# TopLevel.net
KiCad netlist of a schematic drawn in Altium Designer
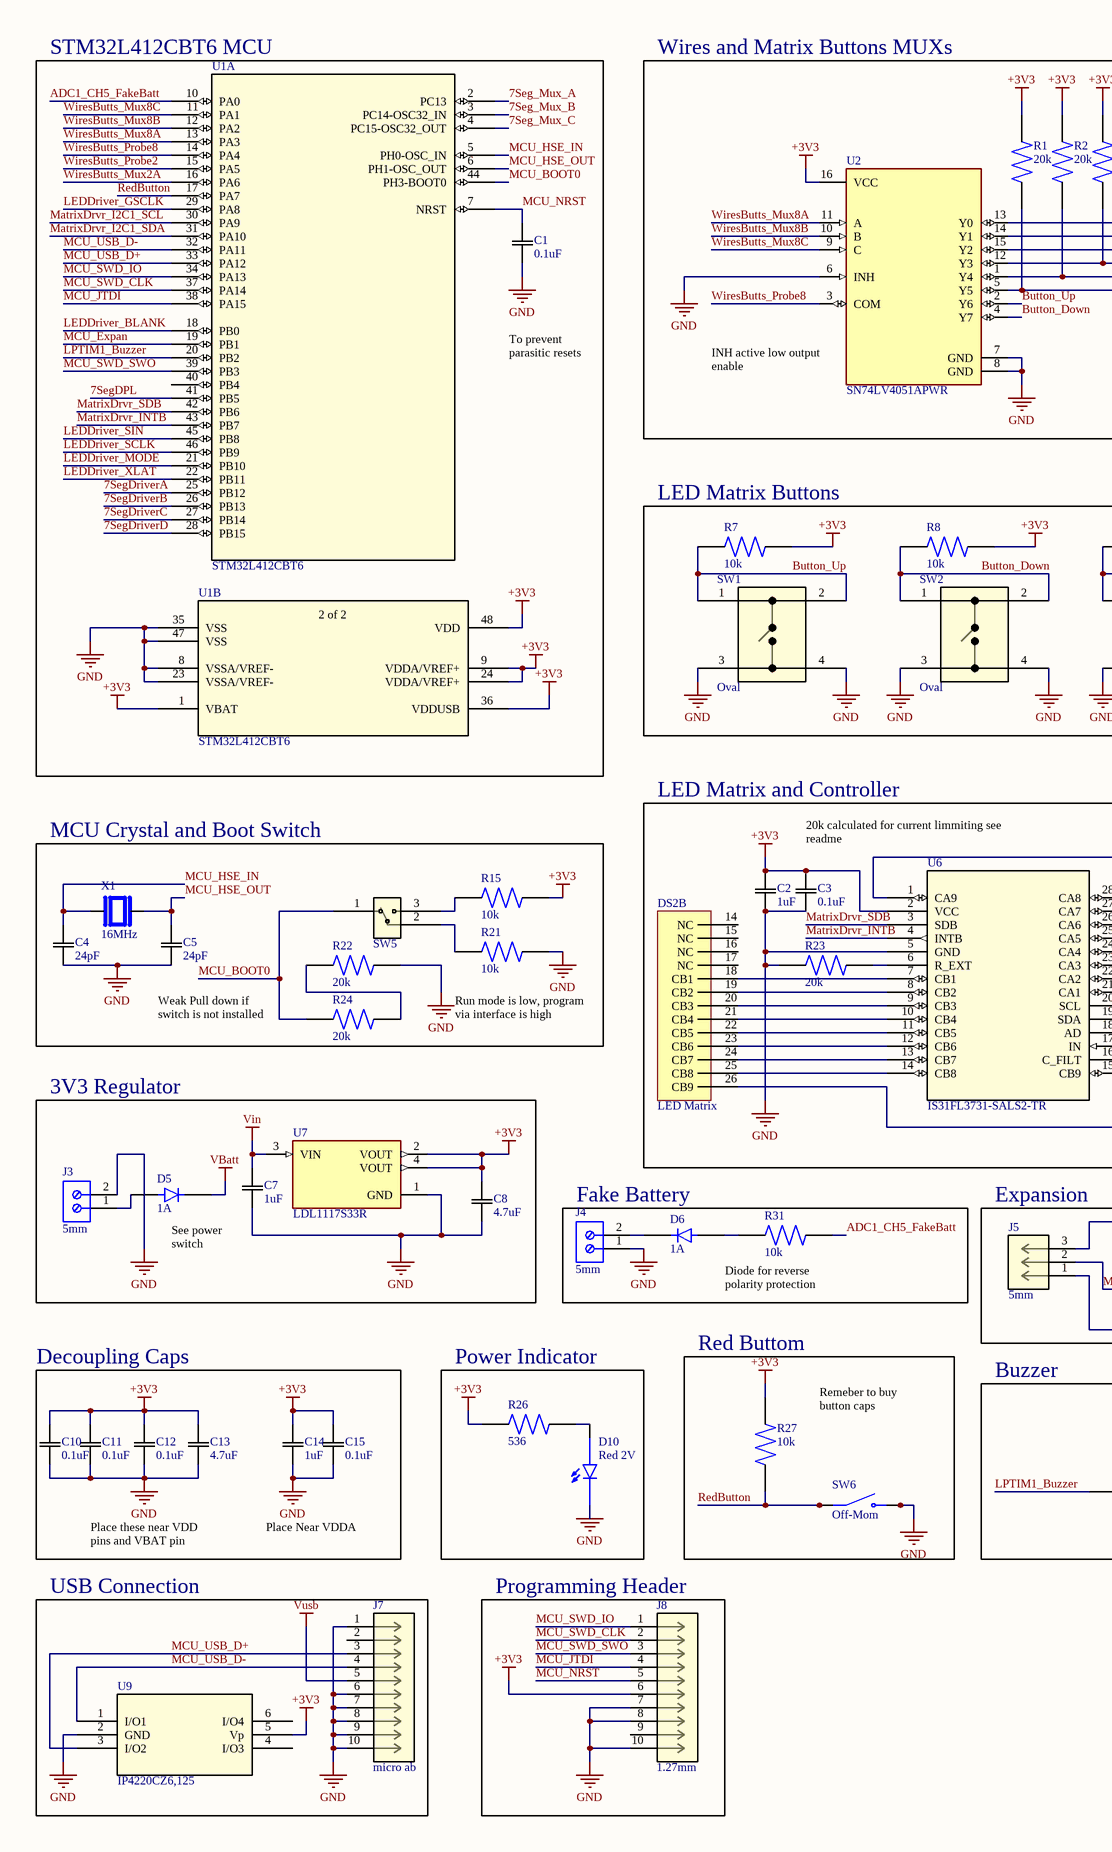
[diagram p0: TopLevel.SchDoc, left]
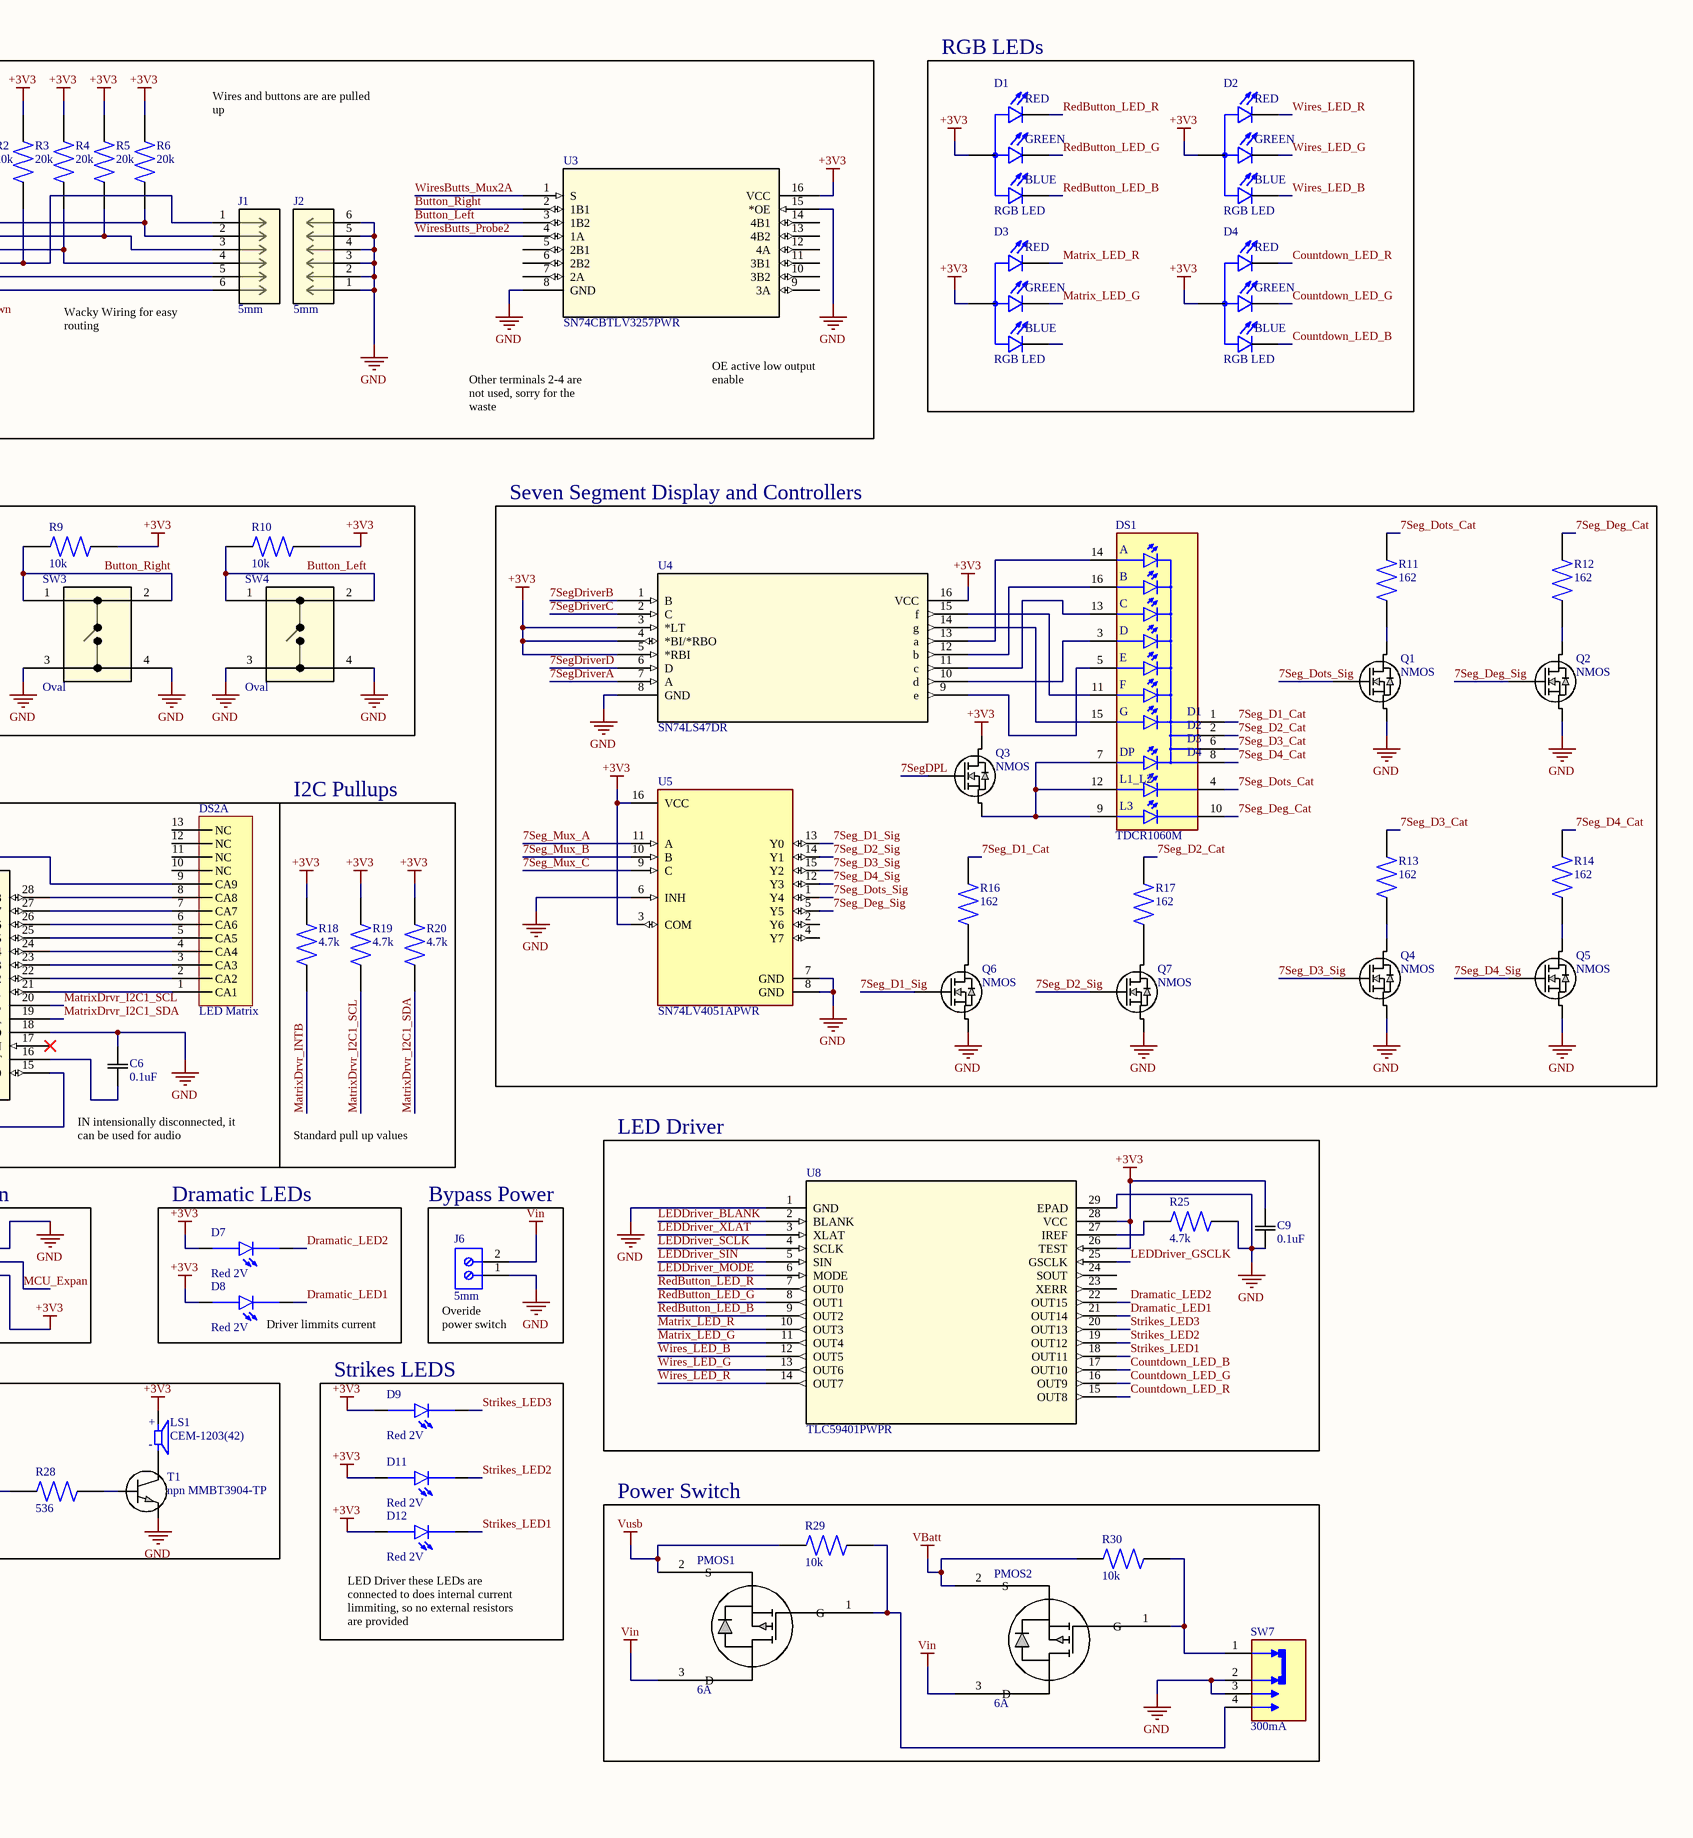
[diagram p1: TopLevel.SchDoc, right]

(export (version "E")
  (design (tool "Eeschema 10.0.6"))
  (components
    (comp (ref "C1")
      (value "0.1uF")
      (footprint "0805")
      (fields
        (field (name "MANUFACTURER") "Yageo")
        (field (name "MANUFACTURER PART NUMBER") "CC0805KRX7R9BB104")
      )
      (libsource (lib "Schlib1") (part "CAP CER 0.1uF 50V 0805"))
    )
    (comp (ref "C2")
      (value "1uF")
      (footprint "0805")
      (fields
        (field (name "MANUFACTURER") "Samsung")
        (field (name "MANUFACTURER PART NUMBER") "CL21B105KBFNNNE")
      )
      (libsource (lib "Schlib1") (part "CAP CER 1uF 50V 0805"))
    )
    (comp (ref "C3")
      (value "0.1uF")
      (footprint "0805")
      (fields
        (field (name "MANUFACTURER") "Yageo")
        (field (name "MANUFACTURER PART NUMBER") "CC0805KRX7R9BB104")
      )
      (libsource (lib "Schlib1") (part "CAP CER 0.1uF 50V 0805"))
    )
    (comp (ref "C4")
      (value "24pF")
      (footprint "0805")
      (description "CAP CER 24PF 50V NPO 0805")
      (fields
        (field (name "MANUFACTURER") "Yageo")
        (field (name "MANUFACTURER PART NUMBER") "CC0805JRNPO9BN240")
      )
      (libsource (lib "Schlib1") (part "CAP CER 24pF 5% 50V 0805"))
    )
    (comp (ref "C5")
      (value "24pF")
      (footprint "0805")
      (description "CAP CER 24PF 50V NPO 0805")
      (fields
        (field (name "MANUFACTURER") "Yageo")
        (field (name "MANUFACTURER PART NUMBER") "CC0805JRNPO9BN240")
      )
      (libsource (lib "Schlib1") (part "CAP CER 24pF 5% 50V 0805"))
    )
    (comp (ref "C6")
      (value "0.1uF")
      (footprint "0805")
      (fields
        (field (name "MANUFACTURER") "Yageo")
        (field (name "MANUFACTURER PART NUMBER") "CC0805KRX7R9BB104")
      )
      (libsource (lib "Schlib1") (part "CAP CER 0.1uF 50V 0805"))
    )
    (comp (ref "C7")
      (value "1uF")
      (footprint "0805")
      (fields
        (field (name "MANUFACTURER") "Samsung")
        (field (name "MANUFACTURER PART NUMBER") "CL21B105KBFNNNE")
      )
      (libsource (lib "Schlib1") (part "CAP CER 1uF 50V 0805"))
    )
    (comp (ref "C8")
      (value "4.7uF")
      (footprint "0805")
      (fields
        (field (name "MANUFACTURER") "Samsung")
        (field (name "MANUFACTURER PART NUMBER") "CL21A475KAQNNNE")
      )
      (libsource (lib "Schlib1") (part "CAP CER 4.7uF 50V 0805"))
    )
    (comp (ref "C9")
      (value "0.1uF")
      (footprint "0805")
      (fields
        (field (name "MANUFACTURER") "Yageo")
        (field (name "MANUFACTURER PART NUMBER") "CC0805KRX7R9BB104")
      )
      (libsource (lib "Schlib1") (part "CAP CER 0.1uF 50V 0805"))
    )
    (comp (ref "C10")
      (value "0.1uF")
      (footprint "0805")
      (fields
        (field (name "MANUFACTURER") "Yageo")
        (field (name "MANUFACTURER PART NUMBER") "CC0805KRX7R9BB104")
      )
      (libsource (lib "Schlib1") (part "CAP CER 0.1uF 50V 0805"))
    )
    (comp (ref "C11")
      (value "0.1uF")
      (footprint "0805")
      (fields
        (field (name "MANUFACTURER") "Yageo")
        (field (name "MANUFACTURER PART NUMBER") "CC0805KRX7R9BB104")
      )
      (libsource (lib "Schlib1") (part "CAP CER 0.1uF 50V 0805"))
    )
    (comp (ref "C12")
      (value "0.1uF")
      (footprint "0805")
      (fields
        (field (name "MANUFACTURER") "Yageo")
        (field (name "MANUFACTURER PART NUMBER") "CC0805KRX7R9BB104")
      )
      (libsource (lib "Schlib1") (part "CAP CER 0.1uF 50V 0805"))
    )
    (comp (ref "C13")
      (value "4.7uF")
      (footprint "0805")
      (fields
        (field (name "MANUFACTURER") "Samsung")
        (field (name "MANUFACTURER PART NUMBER") "CL21A475KAQNNNE")
      )
      (libsource (lib "Schlib1") (part "CAP CER 4.7uF 50V 0805"))
    )
    (comp (ref "C14")
      (value "1uF")
      (footprint "0805")
      (fields
        (field (name "MANUFACTURER") "Samsung")
        (field (name "MANUFACTURER PART NUMBER") "CL21B105KBFNNNE")
      )
      (libsource (lib "Schlib1") (part "CAP CER 1uF 50V 0805"))
    )
    (comp (ref "C15")
      (value "0.1uF")
      (footprint "0805")
      (fields
        (field (name "MANUFACTURER") "Yageo")
        (field (name "MANUFACTURER PART NUMBER") "CC0805KRX7R9BB104")
      )
      (libsource (lib "Schlib1") (part "CAP CER 0.1uF 50V 0805"))
    )
    (comp (ref "D1")
      (value "RGB LED")
      (footprint "RBG LED 4-SMD")
      (description "Visible LED")
      (fields
        (field (name "MANUFACTURER") "Cree")
        (field (name "MANUFACTURER PART NUMBER") "CLMVC-FKA-CL1D1L71BB7C3C3")
      )
      (libsource (lib "Schlib1") (part "DI LED RGB ComAnode"))
    )
    (comp (ref "D2")
      (value "RGB LED")
      (footprint "RBG LED 4-SMD")
      (description "Visible LED")
      (fields
        (field (name "MANUFACTURER") "Cree")
        (field (name "MANUFACTURER PART NUMBER") "CLMVC-FKA-CL1D1L71BB7C3C3")
      )
      (libsource (lib "Schlib1") (part "DI LED RGB ComAnode"))
    )
    (comp (ref "D3")
      (value "RGB LED")
      (footprint "RBG LED 4-SMD")
      (description "Visible LED")
      (fields
        (field (name "MANUFACTURER") "Cree")
        (field (name "MANUFACTURER PART NUMBER") "CLMVC-FKA-CL1D1L71BB7C3C3")
      )
      (libsource (lib "Schlib1") (part "DI LED RGB ComAnode"))
    )
    (comp (ref "D4")
      (value "RGB LED")
      (footprint "RBG LED 4-SMD")
      (description "Visible LED")
      (fields
        (field (name "MANUFACTURER") "Cree")
        (field (name "MANUFACTURER PART NUMBER") "CLMVC-FKA-CL1D1L71BB7C3C3")
      )
      (libsource (lib "Schlib1") (part "DI LED RGB ComAnode"))
    )
    (comp (ref "D5")
      (value "1A")
      (footprint "SOD-123F Diode Schottky")
      (description "Rectifier Diode, Schottky, 1 Phase, 1 Element, 1A, 25V V(RRM), Silicon")
      (fields (field (name "MANUFACTURER") "Rohm") (field (name "MANUFACTURER PART NUMBER") "RB161MM-20TR"))
      (libsource (lib "Schlib1") (part "Diode Schottky 25V 1A"))
    )
    (comp (ref "D6")
      (value "1A")
      (footprint "SOD-123F Diode Schottky")
      (description "Rectifier Diode, Schottky, 1 Phase, 1 Element, 1A, 25V V(RRM), Silicon")
      (fields (field (name "MANUFACTURER") "Rohm") (field (name "MANUFACTURER PART NUMBER") "RB161MM-20TR"))
      (libsource (lib "Schlib1") (part "Diode Schottky 25V 1A"))
    )
    (comp (ref "D7")
      (value "Red 2V")
      (footprint "0805")
      (description "Single Color LED, Red Orange, Water Clear, 1.4mm")
      (fields
        (field (name "MANUFACTURER") "Vishay Lite-On")
        (field (name "MANUFACTURER PART NUMBER") "LTST-C170KAKT")
      )
      (libsource (lib "Schlib1") (part "DIO LED RED 2V 0805"))
    )
    (comp (ref "D8")
      (value "Red 2V")
      (footprint "0805")
      (description "Single Color LED, Red Orange, Water Clear, 1.4mm")
      (fields
        (field (name "MANUFACTURER") "Vishay Lite-On")
        (field (name "MANUFACTURER PART NUMBER") "LTST-C170KAKT")
      )
      (libsource (lib "Schlib1") (part "DIO LED RED 2V 0805"))
    )
    (comp (ref "D9")
      (value "Red 2V")
      (footprint "0805")
      (description "Single Color LED, Red Orange, Water Clear, 1.4mm")
      (fields
        (field (name "MANUFACTURER") "Vishay Lite-On")
        (field (name "MANUFACTURER PART NUMBER") "LTST-C170KAKT")
      )
      (libsource (lib "Schlib1") (part "DIO LED RED 2V 0805"))
    )
    (comp (ref "D10")
      (value "Red 2V")
      (footprint "0805")
      (description "Single Color LED, Red Orange, Water Clear, 1.4mm")
      (fields
        (field (name "MANUFACTURER") "Vishay Lite-On")
        (field (name "MANUFACTURER PART NUMBER") "LTST-C170KAKT")
      )
      (libsource (lib "Schlib1") (part "DIO LED RED 2V 0805"))
    )
    (comp (ref "D11")
      (value "Red 2V")
      (footprint "0805")
      (description "Single Color LED, Red Orange, Water Clear, 1.4mm")
      (fields
        (field (name "MANUFACTURER") "Vishay Lite-On")
        (field (name "MANUFACTURER PART NUMBER") "LTST-C170KAKT")
      )
      (libsource (lib "Schlib1") (part "DIO LED RED 2V 0805"))
    )
    (comp (ref "D12")
      (value "Red 2V")
      (footprint "0805")
      (description "Single Color LED, Red Orange, Water Clear, 1.4mm")
      (fields
        (field (name "MANUFACTURER") "Vishay Lite-On")
        (field (name "MANUFACTURER PART NUMBER") "LTST-C170KAKT")
      )
      (libsource (lib "Schlib1") (part "DIO LED RED 2V 0805"))
    )
    (comp (ref "DS1")
      (value "TDCR1060M")
      (footprint "16-DIP 4Char-7Seg")
      (description "Clock LED Display, 4-Character, Red, 10mm")
      (fields (field (name "MANUFACTURER") "Vishay"))
      (libsource (lib "Schlib1") (part "DISP 7-seg 4Char Clock"))
    )
    (comp (ref "DS2")
      (value "LED Matrix")
      (footprint "LED Matrix 9x16 Charlie")
      (libsource (lib "") (part "LEDARR 2973 9X16_1"))
    )
    (comp (ref "J1")
      (value "5mm")
      (footprint "CON 6pos Screw 5.00mm")
      (description "Barrier Strip Terminal Block, 17.5A, 2.5mm2, 1 Row(s), 1 Deck(s)")
      (fields
        (field (name "MANUFACTURER") "Phoenix Contact")
        (field (name "MANUFACTURER PART NUMBER") "1988846")
        (field (name "SAFETY APPROVAL") "UL")
      )
      (libsource (lib "Schlib1") (part "CONN SCREW 6pos 45Deg 5mm"))
    )
    (comp (ref "J2")
      (value "5mm")
      (footprint "CON 6pos Screw 5.00mm")
      (description "Barrier Strip Terminal Block, 17.5A, 2.5mm2, 1 Row(s), 1 Deck(s)")
      (fields
        (field (name "MANUFACTURER") "Phoenix Contact")
        (field (name "MANUFACTURER PART NUMBER") "1988846")
        (field (name "SAFETY APPROVAL") "UL")
      )
      (libsource (lib "") (part "CONN SCREW 6pos 45Deg 5mm_1"))
    )
    (comp (ref "J3")
      (value "5mm")
      (footprint "Con 2Pos Screw 5.00mm")
      (description "Barrier Strip Terminal Block")
      (fields
        (field (name "MANUFACTURER") "Wurth Electronics")
        (field (name "MANUFACTURER PART NUMBER") "691137710002")
      )
      (libsource (lib "Schlib1") (part "CON Screw 2Pos 5.00mm"))
    )
    (comp (ref "J4")
      (value "5mm")
      (footprint "Con 2Pos Screw 5.00mm")
      (description "Barrier Strip Terminal Block")
      (fields
        (field (name "MANUFACTURER") "Wurth Electronics")
        (field (name "MANUFACTURER PART NUMBER") "691137710002")
      )
      (libsource (lib "Schlib1") (part "CON Screw 2Pos 5.00mm"))
    )
    (comp (ref "J5")
      (value "5mm")
      (footprint "CONN 3pos 5.00mm")
      (description "Barrier Strip Terminal Block, 17.5A, 1.5mm2, 1 Row(s), 1 Deck(s)")
      (fields
        (field (name "MANUFACTURER") "Phoenix Contact")
        (field (name "MANUFACTURER PART NUMBER") "1935174")
        (field (name "SAFETY APPROVAL") "UL")
      )
      (libsource (lib "Schlib1") (part "CONN SCREW 3pos 5.0mm"))
    )
    (comp (ref "J6")
      (value "5mm")
      (footprint "Con 2Pos Screw 5.00mm")
      (description "Barrier Strip Terminal Block")
      (fields
        (field (name "MANUFACTURER") "Wurth Electronics")
        (field (name "MANUFACTURER PART NUMBER") "691137710002")
      )
      (libsource (lib "Schlib1") (part "CON Screw 2Pos 5.00mm"))
    )
    (comp (ref "J7")
      (value "micro ab")
      (footprint "USB micro ab 0475900001")
      (description "USB Connector, 5 Contact(s), Female, Right Angle, Surface Mount Terminal, Locking, Receptacle")
      (fields (field (name "MANUFACTURER") "Molex") (field (name "MANUFACTURER PART NUMBER") "47590-0001"))
      (libsource (lib "Schlib1") (part "CON USB micro ab"))
    )
    (comp (ref "J8")
      (value "1.27mm")
      (footprint "Con 10pin 2Row 1.27mm")
      (fields
        (field (name "MANUFACTURER") "Toshiba")
        (field (name "MANUFACTURER PART NUMBER") "SSM3J372R,LF")
      )
      (libsource (lib "Schlib1") (part "Con 10pos 2row Header 1.27mm Surface"))
    )
    (comp (ref "LS1")
      (value "CEM-1203(42)")
      (footprint "Buzzer CEM-1203(42)")
      (description "Audio Signaling/Alarm Devices")
      (fields (field (name "MANUFACTURER") "Same Sky"))
      (libsource (lib "Schlib1") (part "LS Buzzer CEM-1203(42)"))
    )
    (comp (ref "PMOS1")
      (value "6A")
      (footprint "SOT-23F MOS PMOS 30V 6A")
      (fields
        (field (name "MANUFACTURER") "Toshiba")
        (field (name "MANUFACTURER PART NUMBER") "SSM3J372R,LF")
      )
      (libsource (lib "Schlib1") (part "MOS PMOS 30V 6A"))
    )
    (comp (ref "PMOS2")
      (value "6A")
      (footprint "SOT-23F MOS PMOS 30V 6A")
      (fields
        (field (name "MANUFACTURER") "Toshiba")
        (field (name "MANUFACTURER PART NUMBER") "SSM3J372R,LF")
      )
      (libsource (lib "Schlib1") (part "MOS PMOS 30V 6A"))
    )
    (comp (ref "Q1")
      (value "NMOS")
      (footprint "SOT-323 MOS")
      (fields
        (field (name "MANUFACTURER") "Diodes Zetex")
        (field (name "MANUFACTURER PART NUMBER") "DMG1012UW-7")
      )
      (libsource (lib "Schlib1") (part "MOS NMOS 20V 1A SOT323"))
    )
    (comp (ref "Q2")
      (value "NMOS")
      (footprint "SOT-323 MOS")
      (fields
        (field (name "MANUFACTURER") "Diodes Zetex")
        (field (name "MANUFACTURER PART NUMBER") "DMG1012UW-7")
      )
      (libsource (lib "Schlib1") (part "MOS NMOS 20V 1A SOT323"))
    )
    (comp (ref "Q3")
      (value "NMOS")
      (footprint "SOT-323 MOS")
      (fields
        (field (name "MANUFACTURER") "Diodes Zetex")
        (field (name "MANUFACTURER PART NUMBER") "DMG1012UW-7")
      )
      (libsource (lib "Schlib1") (part "MOS NMOS 20V 1A SOT323"))
    )
    (comp (ref "Q4")
      (value "NMOS")
      (footprint "SOT-323 MOS")
      (fields
        (field (name "MANUFACTURER") "Diodes Zetex")
        (field (name "MANUFACTURER PART NUMBER") "DMG1012UW-7")
      )
      (libsource (lib "Schlib1") (part "MOS NMOS 20V 1A SOT323"))
    )
    (comp (ref "Q5")
      (value "NMOS")
      (footprint "SOT-323 MOS")
      (fields
        (field (name "MANUFACTURER") "Diodes Zetex")
        (field (name "MANUFACTURER PART NUMBER") "DMG1012UW-7")
      )
      (libsource (lib "Schlib1") (part "MOS NMOS 20V 1A SOT323"))
    )
    (comp (ref "Q6")
      (value "NMOS")
      (footprint "SOT-323 MOS")
      (fields
        (field (name "MANUFACTURER") "Diodes Zetex")
        (field (name "MANUFACTURER PART NUMBER") "DMG1012UW-7")
      )
      (libsource (lib "Schlib1") (part "MOS NMOS 20V 1A SOT323"))
    )
    (comp (ref "Q7")
      (value "NMOS")
      (footprint "SOT-323 MOS")
      (fields
        (field (name "MANUFACTURER") "Diodes Zetex")
        (field (name "MANUFACTURER PART NUMBER") "DMG1012UW-7")
      )
      (libsource (lib "Schlib1") (part "MOS NMOS 20V 1A SOT323"))
    )
    (comp (ref "R1")
      (value "20k")
      (footprint "0805")
      (description "Fixed Resistor, Thin Film, 0.125W, 20000ohm, 150V, 0.1% +/-Tol, 25ppm/Cel, Surface Mount, 0805")
      (fields
        (field (name "MANUFACTURER") "Susumu")
        (field (name "MANUFACTURER PART NUMBER") "RG2012P-203-B-T5")
      )
      (libsource (lib "Schlib1") (part "RES 20K 0.1% 0.125W 0805"))
    )
    (comp (ref "R2")
      (value "20k")
      (footprint "0805")
      (description "Fixed Resistor, Thin Film, 0.125W, 20000ohm, 150V, 0.1% +/-Tol, 25ppm/Cel, Surface Mount, 0805")
      (fields
        (field (name "MANUFACTURER") "Susumu")
        (field (name "MANUFACTURER PART NUMBER") "RG2012P-203-B-T5")
      )
      (libsource (lib "Schlib1") (part "RES 20K 0.1% 0.125W 0805"))
    )
    (comp (ref "R3")
      (value "20k")
      (footprint "0805")
      (description "Fixed Resistor, Thin Film, 0.125W, 20000ohm, 150V, 0.1% +/-Tol, 25ppm/Cel, Surface Mount, 0805")
      (fields
        (field (name "MANUFACTURER") "Susumu")
        (field (name "MANUFACTURER PART NUMBER") "RG2012P-203-B-T5")
      )
      (libsource (lib "Schlib1") (part "RES 20K 0.1% 0.125W 0805"))
    )
    (comp (ref "R4")
      (value "20k")
      (footprint "0805")
      (description "Fixed Resistor, Thin Film, 0.125W, 20000ohm, 150V, 0.1% +/-Tol, 25ppm/Cel, Surface Mount, 0805")
      (fields
        (field (name "MANUFACTURER") "Susumu")
        (field (name "MANUFACTURER PART NUMBER") "RG2012P-203-B-T5")
      )
      (libsource (lib "Schlib1") (part "RES 20K 0.1% 0.125W 0805"))
    )
    (comp (ref "R5")
      (value "20k")
      (footprint "0805")
      (description "Fixed Resistor, Thin Film, 0.125W, 20000ohm, 150V, 0.1% +/-Tol, 25ppm/Cel, Surface Mount, 0805")
      (fields
        (field (name "MANUFACTURER") "Susumu")
        (field (name "MANUFACTURER PART NUMBER") "RG2012P-203-B-T5")
      )
      (libsource (lib "Schlib1") (part "RES 20K 0.1% 0.125W 0805"))
    )
    (comp (ref "R6")
      (value "20k")
      (footprint "0805")
      (description "Fixed Resistor, Thin Film, 0.125W, 20000ohm, 150V, 0.1% +/-Tol, 25ppm/Cel, Surface Mount, 0805")
      (fields
        (field (name "MANUFACTURER") "Susumu")
        (field (name "MANUFACTURER PART NUMBER") "RG2012P-203-B-T5")
      )
      (libsource (lib "Schlib1") (part "RES 20K 0.1% 0.125W 0805"))
    )
    (comp (ref "R7")
      (value "10k")
      (footprint "0805")
      (fields
        (field (name "MANUFACTURER") "Panasonic")
        (field (name "MANUFACTURER PART NUMBER") "ERJ-6GEYJ103V")
        (field (name "TOLERANCE") "5%")
      )
      (libsource (lib "Schlib1") (part "RES 10k 5% 0.125W 0805"))
    )
    (comp (ref "R8")
      (value "10k")
      (footprint "0805")
      (fields
        (field (name "MANUFACTURER") "Panasonic")
        (field (name "MANUFACTURER PART NUMBER") "ERJ-6GEYJ103V")
        (field (name "TOLERANCE") "5%")
      )
      (libsource (lib "Schlib1") (part "RES 10k 5% 0.125W 0805"))
    )
    (comp (ref "R9")
      (value "10k")
      (footprint "0805")
      (fields
        (field (name "MANUFACTURER") "Panasonic")
        (field (name "MANUFACTURER PART NUMBER") "ERJ-6GEYJ103V")
        (field (name "TOLERANCE") "5%")
      )
      (libsource (lib "Schlib1") (part "RES 10k 5% 0.125W 0805"))
    )
    (comp (ref "R10")
      (value "10k")
      (footprint "0805")
      (fields
        (field (name "MANUFACTURER") "Panasonic")
        (field (name "MANUFACTURER PART NUMBER") "ERJ-6GEYJ103V")
        (field (name "TOLERANCE") "5%")
      )
      (libsource (lib "Schlib1") (part "RES 10k 5% 0.125W 0805"))
    )
    (comp (ref "R11")
      (value "162")
      (footprint "0805")
      (fields
        (field (name "MANUFACTURER") "Yageo")
        (field (name "MANUFACTURER PART NUMBER") "RC0805FR-07162RL")
        (field (name "TOLERANCE") "1%")
      )
      (libsource (lib "Schlib1") (part "RES 162 1% 0.125W 0805"))
    )
    (comp (ref "R12")
      (value "162")
      (footprint "0805")
      (fields
        (field (name "MANUFACTURER") "Yageo")
        (field (name "MANUFACTURER PART NUMBER") "RC0805FR-07162RL")
        (field (name "TOLERANCE") "1%")
      )
      (libsource (lib "Schlib1") (part "RES 162 1% 0.125W 0805"))
    )
    (comp (ref "R13")
      (value "162")
      (footprint "0805")
      (fields
        (field (name "MANUFACTURER") "Yageo")
        (field (name "MANUFACTURER PART NUMBER") "RC0805FR-07162RL")
        (field (name "TOLERANCE") "1%")
      )
      (libsource (lib "Schlib1") (part "RES 162 1% 0.125W 0805"))
    )
    (comp (ref "R14")
      (value "162")
      (footprint "0805")
      (fields
        (field (name "MANUFACTURER") "Yageo")
        (field (name "MANUFACTURER PART NUMBER") "RC0805FR-07162RL")
        (field (name "TOLERANCE") "1%")
      )
      (libsource (lib "Schlib1") (part "RES 162 1% 0.125W 0805"))
    )
    (comp (ref "R15")
      (value "10k")
      (footprint "0805")
      (fields
        (field (name "MANUFACTURER") "Panasonic")
        (field (name "MANUFACTURER PART NUMBER") "ERJ-6GEYJ103V")
        (field (name "TOLERANCE") "5%")
      )
      (libsource (lib "Schlib1") (part "RES 10k 5% 0.125W 0805"))
    )
    (comp (ref "R16")
      (value "162")
      (footprint "0805")
      (fields
        (field (name "MANUFACTURER") "Yageo")
        (field (name "MANUFACTURER PART NUMBER") "RC0805FR-07162RL")
        (field (name "TOLERANCE") "1%")
      )
      (libsource (lib "Schlib1") (part "RES 162 1% 0.125W 0805"))
    )
    (comp (ref "R17")
      (value "162")
      (footprint "0805")
      (fields
        (field (name "MANUFACTURER") "Yageo")
        (field (name "MANUFACTURER PART NUMBER") "RC0805FR-07162RL")
        (field (name "TOLERANCE") "1%")
      )
      (libsource (lib "Schlib1") (part "RES 162 1% 0.125W 0805"))
    )
    (comp (ref "R18")
      (value "4.7k")
      (footprint "0805")
      (fields
        (field (name "MANUFACTURER") "Vishay")
        (field (name "MANUFACTURER PART NUMBER") "CRCW08054K70FKEA")
        (field (name "TOLERANCE") "1%")
      )
      (libsource (lib "Schlib1") (part "RES 4.7k 1% 0.125W 0805"))
    )
    (comp (ref "R19")
      (value "4.7k")
      (footprint "0805")
      (fields
        (field (name "MANUFACTURER") "Vishay")
        (field (name "MANUFACTURER PART NUMBER") "CRCW08054K70FKEA")
        (field (name "TOLERANCE") "1%")
      )
      (libsource (lib "Schlib1") (part "RES 4.7k 1% 0.125W 0805"))
    )
    (comp (ref "R20")
      (value "4.7k")
      (footprint "0805")
      (fields
        (field (name "MANUFACTURER") "Vishay")
        (field (name "MANUFACTURER PART NUMBER") "CRCW08054K70FKEA")
        (field (name "TOLERANCE") "1%")
      )
      (libsource (lib "Schlib1") (part "RES 4.7k 1% 0.125W 0805"))
    )
    (comp (ref "R21")
      (value "10k")
      (footprint "0805")
      (fields
        (field (name "MANUFACTURER") "Panasonic")
        (field (name "MANUFACTURER PART NUMBER") "ERJ-6GEYJ103V")
        (field (name "TOLERANCE") "5%")
      )
      (libsource (lib "Schlib1") (part "RES 10k 5% 0.125W 0805"))
    )
    (comp (ref "R22")
      (value "20k")
      (footprint "0805")
      (description "Fixed Resistor, Thin Film, 0.125W, 20000ohm, 150V, 0.1% +/-Tol, 25ppm/Cel, Surface Mount, 0805")
      (fields
        (field (name "MANUFACTURER") "Susumu")
        (field (name "MANUFACTURER PART NUMBER") "RG2012P-203-B-T5")
      )
      (libsource (lib "Schlib1") (part "RES 20K 0.1% 0.125W 0805"))
    )
    (comp (ref "R23")
      (value "20k")
      (footprint "0805")
      (description "Fixed Resistor, Thin Film, 0.125W, 20000ohm, 150V, 0.1% +/-Tol, 25ppm/Cel, Surface Mount, 0805")
      (fields
        (field (name "MANUFACTURER") "Susumu")
        (field (name "MANUFACTURER PART NUMBER") "RG2012P-203-B-T5")
      )
      (libsource (lib "Schlib1") (part "RES 20K 0.1% 0.125W 0805"))
    )
    (comp (ref "R24")
      (value "20k")
      (footprint "0805")
      (description "Fixed Resistor, Thin Film, 0.125W, 20000ohm, 150V, 0.1% +/-Tol, 25ppm/Cel, Surface Mount, 0805")
      (fields
        (field (name "MANUFACTURER") "Susumu")
        (field (name "MANUFACTURER PART NUMBER") "RG2012P-203-B-T5")
      )
      (libsource (lib "Schlib1") (part "RES 20K 0.1% 0.125W 0805"))
    )
    (comp (ref "R25")
      (value "4.7k")
      (footprint "0805")
      (fields
        (field (name "MANUFACTURER") "Vishay")
        (field (name "MANUFACTURER PART NUMBER") "CRCW08054K70FKEA")
        (field (name "TOLERANCE") "1%")
      )
      (libsource (lib "Schlib1") (part "RES 4.7k 1% 0.125W 0805"))
    )
    (comp (ref "R26")
      (value "536")
      (footprint "0805")
      (fields
        (field (name "MANUFACTURER") "Yageo")
        (field (name "MANUFACTURER PART NUMBER") "RC0805FR-07536RL")
        (field (name "TOLERANCE") "1%")
      )
      (libsource (lib "Schlib1") (part "RES 536 1% 0.125W 0805"))
    )
    (comp (ref "R27")
      (value "10k")
      (footprint "0805")
      (fields
        (field (name "MANUFACTURER") "Panasonic")
        (field (name "MANUFACTURER PART NUMBER") "ERJ-6GEYJ103V")
        (field (name "TOLERANCE") "5%")
      )
      (libsource (lib "Schlib1") (part "RES 10k 5% 0.125W 0805"))
    )
    (comp (ref "R28")
      (value "536")
      (footprint "0805")
      (fields
        (field (name "MANUFACTURER") "Yageo")
        (field (name "MANUFACTURER PART NUMBER") "RC0805FR-07536RL")
        (field (name "TOLERANCE") "1%")
      )
      (libsource (lib "Schlib1") (part "RES 536 1% 0.125W 0805"))
    )
    (comp (ref "R29")
      (value "10k")
      (footprint "0805")
      (fields
        (field (name "MANUFACTURER") "Panasonic")
        (field (name "MANUFACTURER PART NUMBER") "ERJ-6GEYJ103V")
        (field (name "TOLERANCE") "5%")
      )
      (libsource (lib "Schlib1") (part "RES 10k 5% 0.125W 0805"))
    )
    (comp (ref "R30")
      (value "10k")
      (footprint "0805")
      (fields
        (field (name "MANUFACTURER") "Panasonic")
        (field (name "MANUFACTURER PART NUMBER") "ERJ-6GEYJ103V")
        (field (name "TOLERANCE") "5%")
      )
      (libsource (lib "Schlib1") (part "RES 10k 5% 0.125W 0805"))
    )
    (comp (ref "R31")
      (value "10k")
      (footprint "0805")
      (fields
        (field (name "MANUFACTURER") "Panasonic")
        (field (name "MANUFACTURER PART NUMBER") "ERJ-6GEYJ103V")
        (field (name "TOLERANCE") "5%")
      )
      (libsource (lib "Schlib1") (part "RES 10k 5% 0.125W 0805"))
    )
    (comp (ref "SW1")
      (value "Oval")
      (footprint "Oval Button")
      (fields
        (field (name "MANUFACTURER") "E-Switch")
        (field (name "MANUFACTURER PART NUMBER") "TL3365AF180QG")
      )
      (libsource (lib "Schlib1") (part "SW Off-Mom OvalPush"))
    )
    (comp (ref "SW2")
      (value "Oval")
      (footprint "Oval Button")
      (fields
        (field (name "MANUFACTURER") "E-Switch")
        (field (name "MANUFACTURER PART NUMBER") "TL3365AF180QG")
      )
      (libsource (lib "Schlib1") (part "SW Off-Mom OvalPush"))
    )
    (comp (ref "SW3")
      (value "Oval")
      (footprint "Oval Button")
      (fields
        (field (name "MANUFACTURER") "E-Switch")
        (field (name "MANUFACTURER PART NUMBER") "TL3365AF180QG")
      )
      (libsource (lib "Schlib1") (part "SW Off-Mom OvalPush"))
    )
    (comp (ref "SW4")
      (value "Oval")
      (footprint "Oval Button")
      (fields
        (field (name "MANUFACTURER") "E-Switch")
        (field (name "MANUFACTURER PART NUMBER") "TL3365AF180QG")
      )
      (libsource (lib "Schlib1") (part "SW Off-Mom OvalPush"))
    )
    (comp (ref "SW5")
      (value "OS102011MA1QN1")
      (footprint "OS102011MA1QN1")
      (fields
        (field (name "MANUFACTURER") "ITT C&K")
        (field (name "MANUFACTURER PART NUMBER") "OS102011MA1QN1C")
      )
      (libsource (lib "Schlib1") (part "SW 2pos Through RightAngle"))
    )
    (comp (ref "SW6")
      (value "Off-Mom")
      (footprint "Switch off-Mom")
      (description "Pushbutton Switch, SPST, Momentary-tactile, 0.05A, Solder Terminal, Through Hole-straight")
      (fields
        (field (name "MANUFACTURER") "TE Connectivity Alcoswitch")
        (field (name "MANUFACTURER PART NUMBER") "FSM103")
      )
      (libsource (lib "Schlib1") (part "SW Off-Mom Through"))
    )
    (comp (ref "SW7")
      (value "300mA")
      (footprint "Switch On-On-On 300mA SLW-1277545-2A-RA-S-D")
      (description "12.7 x 7.5 x 4.5 mm, 2 mm Raised Slide Actuator, Right Angle, Through Hole, Slide Switch")
      (fields
        (field (name "MANUFACTURER") "Same Sky")
        (field (name "MANUFACTURER PART NUMBER") "SLW-1277545-2A-RA-S-D")
      )
      (libsource (lib "Schlib1") (part "SW On-On-On 300mA"))
    )
    (comp (ref "T1")
      (value "npn MMBT3904-TP")
      (footprint "SOT-23 Transistor")
      (description "Small Signal Bipolar Transistor, 0.2A I(C), 40V V(BR)CEO, 1-Element, NPN, Silicon")
      (fields (field (name "MANUFACTURER") "MCC") (field (name "MANUFACTURER PART NUMBER") "MMBT3904-TP"))
      (libsource (lib "Schlib1") (part "T npn 40V 0.2A"))
    )
    (comp (ref "U1")
      (value "STM32L412CBT6")
      (footprint "48-LQFP")
      (description "RISC Microcontroller")
      (fields (field (name "MANUFACTURER") "STMicroelectronics"))
      (libsource (lib "Schlib1") (part "IC STM32L412CBT6"))
    )
    (comp (ref "U2")
      (value "SN74LV4051APWR")
      (footprint "16-TSSOP MUX 8to1")
      (description "Single-Ended Multiplexer, 1 Func, 8 Channel, CMOS, PDSO16")
      (fields (field (name "MANUFACTURER") "Texas Instruments"))
      (libsource (lib "Schlib1") (part "IC MUX 8{colon}1 SN74LV4051APWR"))
    )
    (comp (ref "U3")
      (value "SN74CBTLV3257PWR")
      (footprint "16-TSSOP 1:2 switch SN74CBTLV3257PWR")
      (fields (field (name "MANUFACTURER") "Texas Instruments"))
      (libsource (lib "Schlib1") (part "IC 1{colon}2 Switch SN74CBTLV3257PWR"))
    )
    (comp (ref "U4")
      (value "SN74LS47DR")
      (footprint "16-SOIC 7-seg Driver")
      (description "Seven Segment Decoder/Driver, LS Series, Inverted Output, TTL, PDSO16")
      (fields (field (name "MANUFACTURER") "Texas Instruments"))
      (libsource (lib "Schlib1") (part "IC DRVR 7 SEG SN74LS47DR"))
    )
    (comp (ref "U5")
      (value "SN74LV4051APWR")
      (footprint "16-TSSOP MUX 8to1")
      (description "Single-Ended Multiplexer, 1 Func, 8 Channel, CMOS, PDSO16")
      (fields (field (name "MANUFACTURER") "Texas Instruments"))
      (libsource (lib "Schlib1") (part "IC MUX 8{colon}1 SN74LV4051APWR"))
    )
    (comp (ref "U6")
      (value "IS31FL3731-SALS2-TR")
      (footprint "28-SSOP LED Matrix Driver")
      (description "LED Driver, 144-Segment, PDSO28")
      (fields (field (name "MANUFACTURER") "ISSI"))
      (libsource (lib "Schlib1") (part "IC MatrixDriv IS31FL3731-SALS2-TR"))
    )
    (comp (ref "U7")
      (value "LDL1117S33R")
      (footprint "SOT-223 Lin Reg 3V3")
      (description "Fixed Positive LDO Regulator, 3.3V, 0.6V Dropout, PDSO4")
      (fields (field (name "MANUFACTURER") "STMicroelectronics"))
      (libsource (lib "Schlib1") (part "IC LIN REG 3V3 LDL1117S33R"))
    )
    (comp (ref "U8")
      (value "TLC59401PWPR")
      (footprint "28-HTSSOP 16LED Driver")
      (description "LED Driver, 16-Segment, PDSO28")
      (fields (field (name "MANUFACTURER") "Texas Instruments"))
      (libsource (lib "Schlib1") (part "IC 16LED Driver TLC59401PWPR"))
    )
    (comp (ref "U9")
      (value "IP4220CZ6,125")
      (footprint "SOT-457 USB ESD")
      (description "Trans Voltage Suppressor Diode, Unidirectional, 1 Element, Silicon")
      (fields (field (name "MANUFACTURER") "Nexperia"))
      (libsource (lib "Schlib1") (part "IC USB Dual ESD Protec IP4220CZ6,125"))
    )
    (comp (ref "X1")
      (value "16MHz")
      (footprint "OSC 16MHz")
      (description "Crystal 16MHz ±20ppm (Tol) ±50ppm (Stability) 18pF FUND 40Ohm 2-Pin HC-49/US SMD T/R")
      (fields
        (field (name "MANUFACTURER") "Abracon")
        (field (name "MANUFACTURER PART NUMBER") "ABLS-16.000MHZ-B2-T")
      )
      (libsource (lib "Schlib1") (part "OSC 16MHz 18pF"))
    )
  )
  (nets
    (net (code "1") (name "+3V3") (class "Default")
      (node (ref "C10") (pin "2") (pinfunction "2_2") (pintype "passive"))
      (node (ref "C11") (pin "2") (pinfunction "2_2") (pintype "passive"))
      (node (ref "C12") (pin "2") (pinfunction "2_2") (pintype "passive"))
      (node (ref "C13") (pin "2") (pinfunction "2_2") (pintype "passive"))
      (node (ref "C14") (pin "1") (pinfunction "1_1") (pintype "passive"))
      (node (ref "C15") (pin "2") (pinfunction "2_2") (pintype "passive"))
      (node (ref "C2") (pin "2") (pinfunction "2_2") (pintype "passive"))
      (node (ref "C3") (pin "2") (pinfunction "2_2") (pintype "passive"))
      (node (ref "C8") (pin "2") (pinfunction "2_2") (pintype "passive"))
      (node (ref "C9") (pin "2") (pinfunction "2_2") (pintype "passive"))
      (node (ref "D1") (pin "1") (pinfunction "A_1") (pintype "passive"))
      (node (ref "D11") (pin "1") (pinfunction "A_1") (pintype "passive"))
      (node (ref "D12") (pin "1") (pinfunction "A_1") (pintype "passive"))
      (node (ref "D2") (pin "1") (pinfunction "A_1") (pintype "passive"))
      (node (ref "D3") (pin "1") (pinfunction "A_1") (pintype "passive"))
      (node (ref "D4") (pin "1") (pinfunction "A_1") (pintype "passive"))
      (node (ref "D7") (pin "1") (pinfunction "A_1") (pintype "passive"))
      (node (ref "D8") (pin "1") (pinfunction "A_1") (pintype "passive"))
      (node (ref "D9") (pin "1") (pinfunction "A_1") (pintype "passive"))
      (node (ref "J5") (pin "1") (pinfunction "1_1") (pintype "passive"))
      (node (ref "J8") (pin "6") (pinfunction "6_6") (pintype "passive"))
      (node (ref "LS1") (pin "P") (pinfunction "P_P") (pintype "passive"))
      (node (ref "Q3") (pin "2") (pinfunction "D_2") (pintype "passive"))
      (node (ref "R1") (pin "2") (pinfunction "2_2") (pintype "passive"))
      (node (ref "R10") (pin "2") (pinfunction "2_2") (pintype "passive"))
      (node (ref "R15") (pin "2") (pinfunction "2_2") (pintype "passive"))
      (node (ref "R18") (pin "2") (pinfunction "2_2") (pintype "passive"))
      (node (ref "R19") (pin "2") (pinfunction "2_2") (pintype "passive"))
      (node (ref "R2") (pin "2") (pinfunction "2_2") (pintype "passive"))
      (node (ref "R20") (pin "2") (pinfunction "2_2") (pintype "passive"))
      (node (ref "R26") (pin "1") (pinfunction "1_1") (pintype "passive"))
      (node (ref "R27") (pin "2") (pinfunction "2_2") (pintype "passive"))
      (node (ref "R3") (pin "2") (pinfunction "2_2") (pintype "passive"))
      (node (ref "R4") (pin "2") (pinfunction "2_2") (pintype "passive"))
      (node (ref "R5") (pin "2") (pinfunction "2_2") (pintype "passive"))
      (node (ref "R6") (pin "2") (pinfunction "2_2") (pintype "passive"))
      (node (ref "R7") (pin "2") (pinfunction "2_2") (pintype "passive"))
      (node (ref "R8") (pin "2") (pinfunction "2_2") (pintype "passive"))
      (node (ref "R9") (pin "2") (pinfunction "2_2") (pintype "passive"))
      (node (ref "U1") (pin "1") (pinfunction "VBAT_1") (pintype "power_in"))
      (node (ref "U1") (pin "24") (pinfunction "VDDA/VREF+_24") (pintype "power_in"))
      (node (ref "U1") (pin "36") (pinfunction "VDDUSB_36") (pintype "power_in"))
      (node (ref "U1") (pin "48") (pinfunction "VDD_48") (pintype "power_in"))
      (node (ref "U1") (pin "9") (pinfunction "VDDA/VREF+_9") (pintype "power_in"))
      (node (ref "U2") (pin "16") (pinfunction "VCC_16") (pintype "power_in"))
      (node (ref "U3") (pin "16") (pinfunction "VCC_16") (pintype "power_in"))
      (node (ref "U4") (pin "16") (pinfunction "VCC_16") (pintype "power_in"))
      (node (ref "U4") (pin "3") (pinfunction "*LT_3") (pintype "input"))
      (node (ref "U4") (pin "4") (pinfunction "*BI/*RBO_4") (pintype "bidirectional"))
      (node (ref "U4") (pin "5") (pinfunction "*RBI_5") (pintype "input"))
      (node (ref "U5") (pin "16") (pinfunction "VCC_16") (pintype "power_in"))
      (node (ref "U5") (pin "3") (pinfunction "COM_3") (pintype "bidirectional"))
      (node (ref "U6") (pin "2") (pinfunction "VCC_2") (pintype "power_in"))
      (node (ref "U7") (pin "2") (pinfunction "VOUT_2") (pintype "output"))
      (node (ref "U7") (pin "4") (pinfunction "VOUT_4") (pintype "output"))
      (node (ref "U8") (pin "26") (pinfunction "TEST_26") (pintype "input"))
      (node (ref "U8") (pin "28") (pinfunction "VCC_28") (pintype "power_in"))
      (node (ref "U9") (pin "5") (pinfunction "Vp_5") (pintype "passive"))
    )
    (net (code "2") (name "/7SegDPL") (class "Default")
      (node (ref "Q3") (pin "1") (pinfunction "G_1") (pintype "passive"))
      (node (ref "U1") (pin "41") (pinfunction "PB5_41") (pintype "bidirectional"))
    )
    (net (code "3") (name "/7SegDriverA") (class "Default")
      (node (ref "U1") (pin "25") (pinfunction "PB12_25") (pintype "bidirectional"))
      (node (ref "U4") (pin "7") (pinfunction "A_7") (pintype "input"))
    )
    (net (code "4") (name "/7SegDriverB") (class "Default")
      (node (ref "U1") (pin "26") (pinfunction "PB13_26") (pintype "bidirectional"))
      (node (ref "U4") (pin "1") (pinfunction "B_1") (pintype "input"))
    )
    (net (code "5") (name "/7SegDriverC") (class "Default")
      (node (ref "U1") (pin "27") (pinfunction "PB14_27") (pintype "bidirectional"))
      (node (ref "U4") (pin "2") (pinfunction "C_2") (pintype "input"))
    )
    (net (code "6") (name "/7SegDriverD") (class "Default")
      (node (ref "U1") (pin "28") (pinfunction "PB15_28") (pintype "bidirectional"))
      (node (ref "U4") (pin "6") (pinfunction "D_6") (pintype "input"))
    )
    (net (code "7") (name "/7Seg_D1_Cat") (class "Default")
      (node (ref "DS1") (pin "1") (pinfunction "D1_1") (pintype "passive"))
      (node (ref "R16") (pin "2") (pinfunction "2_2") (pintype "passive"))
    )
    (net (code "8") (name "/7Seg_D1_Sig") (class "Default")
      (node (ref "Q6") (pin "1") (pinfunction "G_1") (pintype "passive"))
      (node (ref "U5") (pin "13") (pinfunction "Y0_13") (pintype "bidirectional"))
    )
    (net (code "9") (name "/7Seg_D2_Cat") (class "Default")
      (node (ref "DS1") (pin "2") (pinfunction "D2_2") (pintype "passive"))
      (node (ref "R17") (pin "2") (pinfunction "2_2") (pintype "passive"))
    )
    (net (code "10") (name "/7Seg_D2_Sig") (class "Default")
      (node (ref "Q7") (pin "1") (pinfunction "G_1") (pintype "passive"))
      (node (ref "U5") (pin "14") (pinfunction "Y1_14") (pintype "bidirectional"))
    )
    (net (code "11") (name "/7Seg_D3_Cat") (class "Default")
      (node (ref "DS1") (pin "6") (pinfunction "D3_6") (pintype "passive"))
      (node (ref "R13") (pin "2") (pinfunction "2_2") (pintype "passive"))
    )
    (net (code "12") (name "/7Seg_D3_Sig") (class "Default")
      (node (ref "Q4") (pin "1") (pinfunction "G_1") (pintype "passive"))
      (node (ref "U5") (pin "15") (pinfunction "Y2_15") (pintype "bidirectional"))
    )
    (net (code "13") (name "/7Seg_D4_Cat") (class "Default")
      (node (ref "DS1") (pin "8") (pinfunction "D4_8") (pintype "passive"))
      (node (ref "R14") (pin "2") (pinfunction "2_2") (pintype "passive"))
    )
    (net (code "14") (name "/7Seg_D4_Sig") (class "Default")
      (node (ref "Q5") (pin "1") (pinfunction "G_1") (pintype "passive"))
      (node (ref "U5") (pin "12") (pinfunction "Y3_12") (pintype "bidirectional"))
    )
    (net (code "15") (name "/7Seg_Deg_Cat") (class "Default")
      (node (ref "DS1") (pin "10") (pinfunction "10_10") (pintype "passive"))
      (node (ref "R12") (pin "2") (pinfunction "2_2") (pintype "passive"))
    )
    (net (code "16") (name "/7Seg_Deg_Sig") (class "Default")
      (node (ref "Q2") (pin "1") (pinfunction "G_1") (pintype "passive"))
      (node (ref "U5") (pin "5") (pinfunction "Y5_5") (pintype "bidirectional"))
    )
    (net (code "17") (name "/7Seg_Dots_Cat") (class "Default")
      (node (ref "DS1") (pin "4") (pinfunction "4_4") (pintype "passive"))
      (node (ref "R11") (pin "2") (pinfunction "2_2") (pintype "passive"))
    )
    (net (code "18") (name "/7Seg_Dots_Sig") (class "Default")
      (node (ref "Q1") (pin "1") (pinfunction "G_1") (pintype "passive"))
      (node (ref "U5") (pin "1") (pinfunction "Y4_1") (pintype "bidirectional"))
    )
    (net (code "19") (name "/7Seg_Mux_A") (class "Default")
      (node (ref "U1") (pin "2") (pinfunction "PC13_2") (pintype "bidirectional"))
      (node (ref "U5") (pin "11") (pinfunction "A_11") (pintype "input"))
    )
    (net (code "20") (name "/7Seg_Mux_B") (class "Default")
      (node (ref "U1") (pin "3") (pinfunction "PC14-OSC32_IN_3") (pintype "bidirectional"))
      (node (ref "U5") (pin "10") (pinfunction "B_10") (pintype "input"))
    )
    (net (code "21") (name "/7Seg_Mux_C") (class "Default")
      (node (ref "U1") (pin "4") (pinfunction "PC15-OSC32_OUT_4") (pintype "bidirectional"))
      (node (ref "U5") (pin "9") (pinfunction "C_9") (pintype "input"))
    )
    (net (code "22") (name "/ADC1_CH5_FakeBatt") (class "Default")
      (node (ref "R31") (pin "2") (pinfunction "2_2") (pintype "passive"))
      (node (ref "U1") (pin "10") (pinfunction "PA0_10") (pintype "bidirectional"))
    )
    (net (code "23") (name "/Button_Down") (class "Default")
      (node (ref "R8") (pin "1") (pinfunction "1_1") (pintype "passive"))
      (node (ref "SW2") (pin "1") (pinfunction "1_1") (pintype "passive"))
      (node (ref "SW2") (pin "2") (pinfunction "2_2") (pintype "passive"))
      (node (ref "U2") (pin "4") (pinfunction "Y7_4") (pintype "bidirectional"))
    )
    (net (code "24") (name "/Button_Left") (class "Default")
      (node (ref "R10") (pin "1") (pinfunction "1_1") (pintype "passive"))
      (node (ref "SW4") (pin "1") (pinfunction "1_1") (pintype "passive"))
      (node (ref "SW4") (pin "2") (pinfunction "2_2") (pintype "passive"))
      (node (ref "U3") (pin "3") (pinfunction "1B2_3") (pintype "bidirectional"))
    )
    (net (code "25") (name "/Button_Right") (class "Default")
      (node (ref "R9") (pin "1") (pinfunction "1_1") (pintype "passive"))
      (node (ref "SW3") (pin "1") (pinfunction "1_1") (pintype "passive"))
      (node (ref "SW3") (pin "2") (pinfunction "2_2") (pintype "passive"))
      (node (ref "U3") (pin "2") (pinfunction "1B1_2") (pintype "bidirectional"))
    )
    (net (code "26") (name "/Button_Up") (class "Default")
      (node (ref "R7") (pin "1") (pinfunction "1_1") (pintype "passive"))
      (node (ref "SW1") (pin "1") (pinfunction "1_1") (pintype "passive"))
      (node (ref "SW1") (pin "2") (pinfunction "2_2") (pintype "passive"))
      (node (ref "U2") (pin "2") (pinfunction "Y6_2") (pintype "bidirectional"))
    )
    (net (code "27") (name "/Countdown_LED_B") (class "Default")
      (node (ref "D4") (pin "2") (pinfunction "B_C_2") (pintype "passive"))
      (node (ref "U8") (pin "17") (pinfunction "OUT10_17") (pintype "output"))
    )
    (net (code "28") (name "/Countdown_LED_G") (class "Default")
      (node (ref "D4") (pin "3") (pinfunction "G_C_3") (pintype "passive"))
      (node (ref "U8") (pin "16") (pinfunction "OUT9_16") (pintype "output"))
    )
    (net (code "29") (name "/Countdown_LED_R") (class "Default")
      (node (ref "D4") (pin "4") (pinfunction "R_C_4") (pintype "passive"))
      (node (ref "U8") (pin "15") (pinfunction "OUT8_15") (pintype "output"))
    )
    (net (code "30") (name "/Dramatic_LED1") (class "Default")
      (node (ref "D8") (pin "2") (pinfunction "C_2") (pintype "passive"))
      (node (ref "U8") (pin "21") (pinfunction "OUT14_21") (pintype "output"))
    )
    (net (code "31") (name "/Dramatic_LED2") (class "Default")
      (node (ref "D7") (pin "2") (pinfunction "C_2") (pintype "passive"))
      (node (ref "U8") (pin "22") (pinfunction "OUT15_22") (pintype "output"))
    )
    (net (code "32") (name "/LEDDriver_BLANK") (class "Default")
      (node (ref "U1") (pin "18") (pinfunction "PB0_18") (pintype "bidirectional"))
      (node (ref "U8") (pin "2") (pinfunction "BLANK_2") (pintype "input"))
    )
    (net (code "33") (name "/LEDDriver_GSCLK") (class "Default")
      (node (ref "U1") (pin "29") (pinfunction "PA8_29") (pintype "bidirectional"))
      (node (ref "U8") (pin "25") (pinfunction "GSCLK_25") (pintype "input"))
    )
    (net (code "34") (name "/LEDDriver_MODE") (class "Default")
      (node (ref "U1") (pin "21") (pinfunction "PB10_21") (pintype "bidirectional"))
      (node (ref "U8") (pin "6") (pinfunction "MODE_6") (pintype "input"))
    )
    (net (code "35") (name "/LEDDriver_SCLK") (class "Default")
      (node (ref "U1") (pin "46") (pinfunction "PB9_46") (pintype "bidirectional"))
      (node (ref "U8") (pin "4") (pinfunction "SCLK_4") (pintype "input"))
    )
    (net (code "36") (name "/LEDDriver_SIN") (class "Default")
      (node (ref "U1") (pin "45") (pinfunction "PB8_45") (pintype "bidirectional"))
      (node (ref "U8") (pin "5") (pinfunction "SIN_5") (pintype "input"))
    )
    (net (code "37") (name "/LEDDriver_XLAT") (class "Default")
      (node (ref "U1") (pin "22") (pinfunction "PB11_22") (pintype "bidirectional"))
      (node (ref "U8") (pin "3") (pinfunction "XLAT_3") (pintype "input"))
    )
    (net (code "38") (name "/LPTIM1_Buzzer") (class "Default")
      (node (ref "R28") (pin "1") (pinfunction "1_1") (pintype "passive"))
      (node (ref "U1") (pin "20") (pinfunction "PB2_20") (pintype "bidirectional"))
    )
    (net (code "39") (name "/MCU_BOOT0") (class "Default")
      (node (ref "R24") (pin "2") (pinfunction "2_2") (pintype "passive"))
      (node (ref "SW5") (pin "1") (pinfunction "1_1") (pintype "passive"))
      (node (ref "U1") (pin "44") (pinfunction "PH3-BOOT0_44") (pintype "bidirectional"))
    )
    (net (code "40") (name "/MCU_Expan") (class "Default")
      (node (ref "J5") (pin "2") (pinfunction "2_2") (pintype "passive"))
      (node (ref "U1") (pin "19") (pinfunction "PB1_19") (pintype "bidirectional"))
    )
    (net (code "41") (name "/MCU_HSE_IN") (class "Default")
      (node (ref "C4") (pin "2") (pinfunction "2_2") (pintype "passive"))
      (node (ref "U1") (pin "5") (pinfunction "PH0-OSC_IN_5") (pintype "bidirectional"))
      (node (ref "X1") (pin "1") (pinfunction "1_1") (pintype "passive"))
    )
    (net (code "42") (name "/MCU_HSE_OUT") (class "Default")
      (node (ref "C5") (pin "1") (pinfunction "1_1") (pintype "passive"))
      (node (ref "U1") (pin "6") (pinfunction "PH1-OSC_OUT_6") (pintype "bidirectional"))
      (node (ref "X1") (pin "2") (pinfunction "2_2") (pintype "passive"))
    )
    (net (code "43") (name "/MCU_JTDI") (class "Default")
      (node (ref "J8") (pin "4") (pinfunction "4_4") (pintype "passive"))
      (node (ref "U1") (pin "38") (pinfunction "PA15_38") (pintype "bidirectional"))
    )
    (net (code "44") (name "/MCU_NRST") (class "Default")
      (node (ref "C1") (pin "2") (pinfunction "2_2") (pintype "passive"))
      (node (ref "J8") (pin "5") (pinfunction "5_5") (pintype "passive"))
      (node (ref "U1") (pin "7") (pinfunction "NRST_7") (pintype "bidirectional"))
    )
    (net (code "45") (name "/MCU_SWD_CLK") (class "Default")
      (node (ref "J8") (pin "2") (pinfunction "2_2") (pintype "passive"))
      (node (ref "U1") (pin "37") (pinfunction "PA14_37") (pintype "bidirectional"))
    )
    (net (code "46") (name "/MCU_SWD_IO") (class "Default")
      (node (ref "J8") (pin "1") (pinfunction "1_1") (pintype "passive"))
      (node (ref "U1") (pin "34") (pinfunction "PA13_34") (pintype "bidirectional"))
    )
    (net (code "47") (name "/MCU_SWD_SWO") (class "Default")
      (node (ref "J8") (pin "3") (pinfunction "3_3") (pintype "passive"))
      (node (ref "U1") (pin "39") (pinfunction "PB3_39") (pintype "bidirectional"))
    )
    (net (code "48") (name "/MCU_USB_D+") (class "Default")
      (node (ref "J7") (pin "3") (pinfunction "D+_3") (pintype "passive"))
      (node (ref "U1") (pin "33") (pinfunction "PA12_33") (pintype "bidirectional"))
      (node (ref "U9") (pin "3") (pinfunction "I/O2_3") (pintype "passive"))
    )
    (net (code "49") (name "/MCU_USB_D-") (class "Default")
      (node (ref "J7") (pin "4") (pinfunction "ID_4") (pintype "passive"))
      (node (ref "U1") (pin "32") (pinfunction "PA11_32") (pintype "bidirectional"))
      (node (ref "U9") (pin "1") (pinfunction "I/O1_1") (pintype "passive"))
    )
    (net (code "50") (name "/MatrixDrvr_I2C1_SCL") (class "Default")
      (node (ref "R19") (pin "1") (pinfunction "1_1") (pintype "passive"))
      (node (ref "U1") (pin "30") (pinfunction "PA9_30") (pintype "bidirectional"))
      (node (ref "U6") (pin "20") (pinfunction "SCL_20") (pintype "passive"))
    )
    (net (code "51") (name "/MatrixDrvr_I2C1_SDA") (class "Default")
      (node (ref "R20") (pin "1") (pinfunction "1_1") (pintype "passive"))
      (node (ref "U1") (pin "31") (pinfunction "PA10_31") (pintype "bidirectional"))
      (node (ref "U6") (pin "19") (pinfunction "SDA_19") (pintype "passive"))
    )
    (net (code "52") (name "/MatrixDrvr_INTB") (class "Default")
      (node (ref "R18") (pin "1") (pinfunction "1_1") (pintype "passive"))
      (node (ref "U1") (pin "43") (pinfunction "PB7_43") (pintype "bidirectional"))
      (node (ref "U6") (pin "4") (pinfunction "INTB_4") (pintype "output"))
    )
    (net (code "53") (name "/MatrixDrvr_SDB") (class "Default")
      (node (ref "U1") (pin "42") (pinfunction "PB6_42") (pintype "bidirectional"))
      (node (ref "U6") (pin "3") (pinfunction "SDB_3") (pintype "passive"))
    )
    (net (code "54") (name "/Matrix_LED_G") (class "Default")
      (node (ref "D3") (pin "3") (pinfunction "G_C_3") (pintype "passive"))
      (node (ref "U8") (pin "11") (pinfunction "OUT4_11") (pintype "output"))
    )
    (net (code "55") (name "/Matrix_LED_R") (class "Default")
      (node (ref "D3") (pin "4") (pinfunction "R_C_4") (pintype "passive"))
      (node (ref "U8") (pin "10") (pinfunction "OUT3_10") (pintype "output"))
    )
    (net (code "56") (name "/RedButton") (class "Default")
      (node (ref "R27") (pin "1") (pinfunction "1_1") (pintype "passive"))
      (node (ref "SW6") (pin "1") (pinfunction "COM_1") (pintype "passive"))
      (node (ref "SW6") (pin "2") (pinfunction "COM_2") (pintype "passive"))
      (node (ref "U1") (pin "17") (pinfunction "PA7_17") (pintype "bidirectional"))
    )
    (net (code "57") (name "/RedButton_LED_B") (class "Default")
      (node (ref "D1") (pin "2") (pinfunction "B_C_2") (pintype "passive"))
      (node (ref "U8") (pin "9") (pinfunction "OUT2_9") (pintype "output"))
    )
    (net (code "58") (name "/RedButton_LED_G") (class "Default")
      (node (ref "D1") (pin "3") (pinfunction "G_C_3") (pintype "passive"))
      (node (ref "U8") (pin "8") (pinfunction "OUT1_8") (pintype "output"))
    )
    (net (code "59") (name "/RedButton_LED_R") (class "Default")
      (node (ref "D1") (pin "4") (pinfunction "R_C_4") (pintype "passive"))
      (node (ref "U8") (pin "7") (pinfunction "OUT0_7") (pintype "output"))
    )
    (net (code "60") (name "/Strikes_LED1") (class "Default")
      (node (ref "D12") (pin "2") (pinfunction "C_2") (pintype "passive"))
      (node (ref "U8") (pin "18") (pinfunction "OUT11_18") (pintype "output"))
    )
    (net (code "61") (name "/Strikes_LED2") (class "Default")
      (node (ref "D11") (pin "2") (pinfunction "C_2") (pintype "passive"))
      (node (ref "U8") (pin "19") (pinfunction "OUT12_19") (pintype "output"))
    )
    (net (code "62") (name "/Strikes_LED3") (class "Default")
      (node (ref "D9") (pin "2") (pinfunction "C_2") (pintype "passive"))
      (node (ref "U8") (pin "20") (pinfunction "OUT13_20") (pintype "output"))
    )
    (net (code "63") (name "/WiresButts_Mux2A") (class "Default")
      (node (ref "U1") (pin "16") (pinfunction "PA6_16") (pintype "bidirectional"))
      (node (ref "U3") (pin "1") (pinfunction "S_1") (pintype "input"))
    )
    (net (code "64") (name "/WiresButts_Mux8A") (class "Default")
      (node (ref "U1") (pin "13") (pinfunction "PA3_13") (pintype "bidirectional"))
      (node (ref "U2") (pin "11") (pinfunction "A_11") (pintype "input"))
    )
    (net (code "65") (name "/WiresButts_Mux8B") (class "Default")
      (node (ref "U1") (pin "12") (pinfunction "PA2_12") (pintype "bidirectional"))
      (node (ref "U2") (pin "10") (pinfunction "B_10") (pintype "input"))
    )
    (net (code "66") (name "/WiresButts_Mux8C") (class "Default")
      (node (ref "U1") (pin "11") (pinfunction "PA1_11") (pintype "bidirectional"))
      (node (ref "U2") (pin "9") (pinfunction "C_9") (pintype "input"))
    )
    (net (code "67") (name "/WiresButts_Probe2") (class "Default")
      (node (ref "U1") (pin "15") (pinfunction "PA5_15") (pintype "bidirectional"))
      (node (ref "U3") (pin "4") (pinfunction "1A_4") (pintype "bidirectional"))
    )
    (net (code "68") (name "/WiresButts_Probe8") (class "Default")
      (node (ref "U1") (pin "14") (pinfunction "PA4_14") (pintype "bidirectional"))
      (node (ref "U2") (pin "3") (pinfunction "COM_3") (pintype "bidirectional"))
    )
    (net (code "69") (name "/Wires_LED_B") (class "Default")
      (node (ref "D2") (pin "2") (pinfunction "B_C_2") (pintype "passive"))
      (node (ref "U8") (pin "12") (pinfunction "OUT5_12") (pintype "output"))
    )
    (net (code "70") (name "/Wires_LED_G") (class "Default")
      (node (ref "D2") (pin "3") (pinfunction "G_C_3") (pintype "passive"))
      (node (ref "U8") (pin "13") (pinfunction "OUT6_13") (pintype "output"))
    )
    (net (code "71") (name "/Wires_LED_R") (class "Default")
      (node (ref "D2") (pin "4") (pinfunction "R_C_4") (pintype "passive"))
      (node (ref "U8") (pin "14") (pinfunction "OUT7_14") (pintype "output"))
    )
    (net (code "72") (name "GND") (class "Default")
      (node (ref "C1") (pin "1") (pinfunction "1_1") (pintype "passive"))
      (node (ref "C10") (pin "1") (pinfunction "1_1") (pintype "passive"))
      (node (ref "C11") (pin "1") (pinfunction "1_1") (pintype "passive"))
      (node (ref "C12") (pin "1") (pinfunction "1_1") (pintype "passive"))
      (node (ref "C13") (pin "1") (pinfunction "1_1") (pintype "passive"))
      (node (ref "C14") (pin "2") (pinfunction "2_2") (pintype "passive"))
      (node (ref "C15") (pin "1") (pinfunction "1_1") (pintype "passive"))
      (node (ref "C2") (pin "1") (pinfunction "1_1") (pintype "passive"))
      (node (ref "C3") (pin "1") (pinfunction "1_1") (pintype "passive"))
      (node (ref "C4") (pin "1") (pinfunction "1_1") (pintype "passive"))
      (node (ref "C5") (pin "2") (pinfunction "2_2") (pintype "passive"))
      (node (ref "C6") (pin "2") (pinfunction "2_2") (pintype "passive"))
      (node (ref "C7") (pin "1") (pinfunction "1_1") (pintype "passive"))
      (node (ref "C8") (pin "1") (pinfunction "1_1") (pintype "passive"))
      (node (ref "C9") (pin "1") (pinfunction "1_1") (pintype "passive"))
      (node (ref "D10") (pin "2") (pinfunction "C_2") (pintype "passive"))
      (node (ref "J2") (pin "1") (pinfunction "1_1") (pintype "passive"))
      (node (ref "J2") (pin "2") (pinfunction "2_2") (pintype "passive"))
      (node (ref "J2") (pin "3") (pinfunction "3_3") (pintype "passive"))
      (node (ref "J2") (pin "4") (pinfunction "4_4") (pintype "passive"))
      (node (ref "J2") (pin "5") (pinfunction "5_5") (pintype "passive"))
      (node (ref "J2") (pin "6") (pinfunction "6_6") (pintype "passive"))
      (node (ref "J3") (pin "2") (pinfunction "2_2") (pintype "passive"))
      (node (ref "J4") (pin "1") (pinfunction "1_1") (pintype "passive"))
      (node (ref "J5") (pin "3") (pinfunction "3_3") (pintype "passive"))
      (node (ref "J6") (pin "1") (pinfunction "1_1") (pintype "passive"))
      (node (ref "J7") (pin "1") (pinfunction "VBUS_1") (pintype "passive"))
      (node (ref "J7") (pin "10") (pinfunction "SHIELD_10") (pintype "power_in"))
      (node (ref "J7") (pin "6") (pinfunction "SHIELD_6") (pintype "power_in"))
      (node (ref "J7") (pin "7") (pinfunction "SHIELD_7") (pintype "power_in"))
      (node (ref "J7") (pin "8") (pinfunction "SHIELD_8") (pintype "power_in"))
      (node (ref "J7") (pin "9") (pinfunction "SHIELD_9") (pintype "power_in"))
      (node (ref "J8") (pin "10") (pinfunction "10_10") (pintype "passive"))
      (node (ref "J8") (pin "7") (pinfunction "7_7") (pintype "passive"))
      (node (ref "J8") (pin "8") (pinfunction "8_8") (pintype "passive"))
      (node (ref "Q1") (pin "3") (pinfunction "S_3") (pintype "passive"))
      (node (ref "Q2") (pin "3") (pinfunction "S_3") (pintype "passive"))
      (node (ref "Q4") (pin "3") (pinfunction "S_3") (pintype "passive"))
      (node (ref "Q5") (pin "3") (pinfunction "S_3") (pintype "passive"))
      (node (ref "Q6") (pin "3") (pinfunction "S_3") (pintype "passive"))
      (node (ref "Q7") (pin "3") (pinfunction "S_3") (pintype "passive"))
      (node (ref "R21") (pin "2") (pinfunction "2_2") (pintype "passive"))
      (node (ref "R22") (pin "1") (pinfunction "1_1") (pintype "passive"))
      (node (ref "R23") (pin "1") (pinfunction "1_1") (pintype "passive"))
      (node (ref "R25") (pin "2") (pinfunction "2_2") (pintype "passive"))
      (node (ref "SW1") (pin "3") (pinfunction "3_3") (pintype "passive"))
      (node (ref "SW1") (pin "4") (pinfunction "4_4") (pintype "passive"))
      (node (ref "SW2") (pin "3") (pinfunction "3_3") (pintype "passive"))
      (node (ref "SW2") (pin "4") (pinfunction "4_4") (pintype "passive"))
      (node (ref "SW3") (pin "3") (pinfunction "3_3") (pintype "passive"))
      (node (ref "SW3") (pin "4") (pinfunction "4_4") (pintype "passive"))
      (node (ref "SW4") (pin "3") (pinfunction "3_3") (pintype "passive"))
      (node (ref "SW4") (pin "4") (pinfunction "4_4") (pintype "passive"))
      (node (ref "SW6") (pin "3") (pinfunction "NO_3") (pintype "passive"))
      (node (ref "SW6") (pin "4") (pinfunction "NO_4") (pintype "passive"))
      (node (ref "SW7") (pin "2") (pinfunction "2_2") (pintype "passive"))
      (node (ref "SW7") (pin "3") (pinfunction "3_3") (pintype "passive"))
      (node (ref "T1") (pin "2") (pinfunction "2_2") (pintype "passive"))
      (node (ref "U1") (pin "23") (pinfunction "VSSA/VREF-_23") (pintype "power_in"))
      (node (ref "U1") (pin "35") (pinfunction "VSS_35") (pintype "power_in"))
      (node (ref "U1") (pin "47") (pinfunction "VSS_47") (pintype "power_in"))
      (node (ref "U1") (pin "8") (pinfunction "VSSA/VREF-_8") (pintype "power_in"))
      (node (ref "U2") (pin "6") (pinfunction "INH_6") (pintype "input"))
      (node (ref "U2") (pin "7") (pinfunction "GND_7") (pintype "power_in"))
      (node (ref "U2") (pin "8") (pinfunction "GND_8") (pintype "power_in"))
      (node (ref "U3") (pin "15") (pinfunction "*OE_15") (pintype "input"))
      (node (ref "U3") (pin "8") (pinfunction "GND_8") (pintype "power_in"))
      (node (ref "U4") (pin "8") (pinfunction "GND_8") (pintype "power_in"))
      (node (ref "U5") (pin "6") (pinfunction "INH_6") (pintype "input"))
      (node (ref "U5") (pin "7") (pinfunction "GND_7") (pintype "power_in"))
      (node (ref "U5") (pin "8") (pinfunction "GND_8") (pintype "power_in"))
      (node (ref "U6") (pin "18") (pinfunction "AD_18") (pintype "passive"))
      (node (ref "U6") (pin "5") (pinfunction "GND_5") (pintype "power_in"))
      (node (ref "U7") (pin "1") (pinfunction "GND_1") (pintype "power_in"))
      (node (ref "U8") (pin "1") (pinfunction "GND_1") (pintype "power_in"))
      (node (ref "U8") (pin "29") (pinfunction "EPAD_29") (pintype "passive"))
      (node (ref "U9") (pin "2") (pinfunction "GND_2") (pintype "passive"))
    )
    (net (code "73") (name "Net-(D5-A)") (class "Default")
      (node (ref "D5") (pin "2") (pinfunction "A_2") (pintype "passive"))
      (node (ref "J3") (pin "1") (pinfunction "1_1") (pintype "passive"))
    )
    (net (code "74") (name "Net-(D6-A)") (class "Default")
      (node (ref "D6") (pin "2") (pinfunction "A_2") (pintype "passive"))
      (node (ref "R31") (pin "1") (pinfunction "1_1") (pintype "passive"))
    )
    (net (code "75") (name "Net-(D6-C)") (class "Default")
      (node (ref "D6") (pin "1") (pinfunction "C_1") (pintype "passive"))
      (node (ref "J4") (pin "2") (pinfunction "2_2") (pintype "passive"))
    )
    (net (code "76") (name "Net-(D10-A)") (class "Default")
      (node (ref "D10") (pin "1") (pinfunction "A_1") (pintype "passive"))
      (node (ref "R26") (pin "2") (pinfunction "2_2") (pintype "passive"))
    )
    (net (code "77") (name "Net-(DS1-A)") (class "Default")
      (node (ref "DS1") (pin "14") (pinfunction "A_14") (pintype "passive"))
      (node (ref "U4") (pin "13") (pinfunction "a_13") (pintype "output"))
    )
    (net (code "78") (name "Net-(DS1-B)") (class "Default")
      (node (ref "DS1") (pin "16") (pinfunction "B_16") (pintype "passive"))
      (node (ref "U4") (pin "12") (pinfunction "b_12") (pintype "output"))
    )
    (net (code "79") (name "Net-(DS1-C)") (class "Default")
      (node (ref "DS1") (pin "13") (pinfunction "C_13") (pintype "passive"))
      (node (ref "U4") (pin "11") (pinfunction "c_11") (pintype "output"))
    )
    (net (code "80") (name "Net-(DS1-D)") (class "Default")
      (node (ref "DS1") (pin "3") (pinfunction "D_3") (pintype "passive"))
      (node (ref "U4") (pin "10") (pinfunction "d_10") (pintype "output"))
    )
    (net (code "81") (name "Net-(DS1-DP)") (class "Default")
      (node (ref "DS1") (pin "12") (pinfunction "L1_L2_12") (pintype "passive"))
      (node (ref "DS1") (pin "7") (pinfunction "DP_7") (pintype "passive"))
      (node (ref "DS1") (pin "9") (pinfunction "L3_9") (pintype "passive"))
      (node (ref "Q3") (pin "3") (pinfunction "S_3") (pintype "passive"))
    )
    (net (code "82") (name "Net-(DS1-E)") (class "Default")
      (node (ref "DS1") (pin "5") (pinfunction "E_5") (pintype "passive"))
      (node (ref "U4") (pin "9") (pinfunction "e_9") (pintype "output"))
    )
    (net (code "83") (name "Net-(DS1-F)") (class "Default")
      (node (ref "DS1") (pin "11") (pinfunction "F_11") (pintype "passive"))
      (node (ref "U4") (pin "15") (pinfunction "f_15") (pintype "output"))
    )
    (net (code "84") (name "Net-(DS1-G)") (class "Default")
      (node (ref "DS1") (pin "15") (pinfunction "G_15") (pintype "passive"))
      (node (ref "U4") (pin "14") (pinfunction "g_14") (pintype "output"))
    )
    (net (code "85") (name "Net-(DS2A-CA1)") (class "Default")
      (node (ref "DS2") (pin "1") (pinfunction "CA1_1") (pintype "passive"))
      (node (ref "U6") (pin "21") (pinfunction "CA1_21") (pintype "bidirectional"))
    )
    (net (code "86") (name "Net-(DS2A-CA2)") (class "Default")
      (node (ref "DS2") (pin "2") (pinfunction "CA2_2") (pintype "passive"))
      (node (ref "U6") (pin "22") (pinfunction "CA2_22") (pintype "bidirectional"))
    )
    (net (code "87") (name "Net-(DS2A-CA3)") (class "Default")
      (node (ref "DS2") (pin "3") (pinfunction "CA3_3") (pintype "passive"))
      (node (ref "U6") (pin "23") (pinfunction "CA3_23") (pintype "bidirectional"))
    )
    (net (code "88") (name "Net-(DS2A-CA4)") (class "Default")
      (node (ref "DS2") (pin "4") (pinfunction "CA4_4") (pintype "passive"))
      (node (ref "U6") (pin "24") (pinfunction "CA4_24") (pintype "bidirectional"))
    )
    (net (code "89") (name "Net-(DS2A-CA5)") (class "Default")
      (node (ref "DS2") (pin "5") (pinfunction "CA5_5") (pintype "passive"))
      (node (ref "U6") (pin "25") (pinfunction "CA5_25") (pintype "bidirectional"))
    )
    (net (code "90") (name "Net-(DS2A-CA6)") (class "Default")
      (node (ref "DS2") (pin "6") (pinfunction "CA6_6") (pintype "passive"))
      (node (ref "U6") (pin "26") (pinfunction "CA6_26") (pintype "bidirectional"))
    )
    (net (code "91") (name "Net-(DS2A-CA7)") (class "Default")
      (node (ref "DS2") (pin "7") (pinfunction "CA7_7") (pintype "passive"))
      (node (ref "U6") (pin "27") (pinfunction "CA7_27") (pintype "bidirectional"))
    )
    (net (code "92") (name "Net-(DS2A-CA8)") (class "Default")
      (node (ref "DS2") (pin "8") (pinfunction "CA8_8") (pintype "passive"))
      (node (ref "U6") (pin "28") (pinfunction "CA8_28") (pintype "bidirectional"))
    )
    (net (code "93") (name "Net-(DS2A-CA9)") (class "Default")
      (node (ref "DS2") (pin "9") (pinfunction "CA9_9") (pintype "passive"))
      (node (ref "U6") (pin "1") (pinfunction "CA9_1") (pintype "bidirectional"))
    )
    (net (code "94") (name "Net-(DS2B-CB1)") (class "Default")
      (node (ref "DS2") (pin "18") (pinfunction "CB1_18") (pintype "passive"))
      (node (ref "U6") (pin "7") (pinfunction "CB1_7") (pintype "bidirectional"))
    )
    (net (code "95") (name "Net-(DS2B-CB2)") (class "Default")
      (node (ref "DS2") (pin "19") (pinfunction "CB2_19") (pintype "passive"))
      (node (ref "U6") (pin "8") (pinfunction "CB2_8") (pintype "bidirectional"))
    )
    (net (code "96") (name "Net-(DS2B-CB3)") (class "Default")
      (node (ref "DS2") (pin "20") (pinfunction "CB3_20") (pintype "passive"))
      (node (ref "U6") (pin "9") (pinfunction "CB3_9") (pintype "bidirectional"))
    )
    (net (code "97") (name "Net-(DS2B-CB4)") (class "Default")
      (node (ref "DS2") (pin "21") (pinfunction "CB4_21") (pintype "passive"))
      (node (ref "U6") (pin "10") (pinfunction "CB4_10") (pintype "bidirectional"))
    )
    (net (code "98") (name "Net-(DS2B-CB5)") (class "Default")
      (node (ref "DS2") (pin "22") (pinfunction "CB5_22") (pintype "passive"))
      (node (ref "U6") (pin "11") (pinfunction "CB5_11") (pintype "bidirectional"))
    )
    (net (code "99") (name "Net-(DS2B-CB6)") (class "Default")
      (node (ref "DS2") (pin "23") (pinfunction "CB6_23") (pintype "passive"))
      (node (ref "U6") (pin "12") (pinfunction "CB6_12") (pintype "bidirectional"))
    )
    (net (code "100") (name "Net-(DS2B-CB7)") (class "Default")
      (node (ref "DS2") (pin "24") (pinfunction "CB7_24") (pintype "passive"))
      (node (ref "U6") (pin "13") (pinfunction "CB7_13") (pintype "bidirectional"))
    )
    (net (code "101") (name "Net-(DS2B-CB8)") (class "Default")
      (node (ref "DS2") (pin "25") (pinfunction "CB8_25") (pintype "passive"))
      (node (ref "U6") (pin "14") (pinfunction "CB8_14") (pintype "bidirectional"))
    )
    (net (code "102") (name "Net-(DS2B-CB9)") (class "Default")
      (node (ref "DS2") (pin "26") (pinfunction "CB9_26") (pintype "passive"))
      (node (ref "U6") (pin "15") (pinfunction "CB9_15") (pintype "bidirectional"))
    )
    (net (code "103") (name "Net-(LS1-PadN)") (class "Default")
      (node (ref "LS1") (pin "N") (pinfunction "N_N") (pintype "passive"))
      (node (ref "T1") (pin "3") (pinfunction "3_3") (pintype "passive"))
    )
    (net (code "104") (name "Net-(PMOS1-G)") (class "Default")
      (node (ref "PMOS1") (pin "1") (pinfunction "G_1") (pintype "passive"))
      (node (ref "R29") (pin "2") (pinfunction "2_2") (pintype "passive"))
      (node (ref "SW7") (pin "4") (pinfunction "4_4") (pintype "passive"))
    )
    (net (code "105") (name "Net-(PMOS2-G)") (class "Default")
      (node (ref "PMOS2") (pin "1") (pinfunction "G_1") (pintype "passive"))
      (node (ref "R30") (pin "2") (pinfunction "2_2") (pintype "passive"))
      (node (ref "SW7") (pin "1") (pinfunction "1_1") (pintype "passive"))
    )
    (net (code "106") (name "Net-(Q1-D)") (class "Default")
      (node (ref "Q1") (pin "2") (pinfunction "D_2") (pintype "passive"))
      (node (ref "R11") (pin "1") (pinfunction "1_1") (pintype "passive"))
    )
    (net (code "107") (name "Net-(Q2-D)") (class "Default")
      (node (ref "Q2") (pin "2") (pinfunction "D_2") (pintype "passive"))
      (node (ref "R12") (pin "1") (pinfunction "1_1") (pintype "passive"))
    )
    (net (code "108") (name "Net-(Q4-D)") (class "Default")
      (node (ref "Q4") (pin "2") (pinfunction "D_2") (pintype "passive"))
      (node (ref "R13") (pin "1") (pinfunction "1_1") (pintype "passive"))
    )
    (net (code "109") (name "Net-(Q5-D)") (class "Default")
      (node (ref "Q5") (pin "2") (pinfunction "D_2") (pintype "passive"))
      (node (ref "R14") (pin "1") (pinfunction "1_1") (pintype "passive"))
    )
    (net (code "110") (name "Net-(Q6-D)") (class "Default")
      (node (ref "Q6") (pin "2") (pinfunction "D_2") (pintype "passive"))
      (node (ref "R16") (pin "1") (pinfunction "1_1") (pintype "passive"))
    )
    (net (code "111") (name "Net-(Q7-D)") (class "Default")
      (node (ref "Q7") (pin "2") (pinfunction "D_2") (pintype "passive"))
      (node (ref "R17") (pin "1") (pinfunction "1_1") (pintype "passive"))
    )
    (net (code "112") (name "Net-(R15-Pad1)") (class "Default")
      (node (ref "R15") (pin "1") (pinfunction "1_1") (pintype "passive"))
      (node (ref "SW5") (pin "3") (pinfunction "3_3") (pintype "passive"))
    )
    (net (code "113") (name "Net-(R21-Pad1)") (class "Default")
      (node (ref "R21") (pin "1") (pinfunction "1_1") (pintype "passive"))
      (node (ref "SW5") (pin "2") (pinfunction "2_2") (pintype "passive"))
    )
    (net (code "114") (name "Net-(R22-Pad2)") (class "Default")
      (node (ref "R22") (pin "2") (pinfunction "2_2") (pintype "passive"))
      (node (ref "R24") (pin "1") (pinfunction "1_1") (pintype "passive"))
    )
    (net (code "115") (name "Net-(R28-Pad2)") (class "Default")
      (node (ref "R28") (pin "2") (pinfunction "2_2") (pintype "passive"))
      (node (ref "T1") (pin "1") (pinfunction "1_1") (pintype "passive"))
    )
    (net (code "116") (name "Net-(U2-Y0)") (class "Default")
      (node (ref "J1") (pin "2") (pinfunction "2_2") (pintype "passive"))
      (node (ref "R6") (pin "1") (pinfunction "1_1") (pintype "passive"))
      (node (ref "U2") (pin "13") (pinfunction "Y0_13") (pintype "bidirectional"))
    )
    (net (code "117") (name "Net-(U2-Y1)") (class "Default")
      (node (ref "J1") (pin "3") (pinfunction "3_3") (pintype "passive"))
      (node (ref "R5") (pin "1") (pinfunction "1_1") (pintype "passive"))
      (node (ref "U2") (pin "14") (pinfunction "Y1_14") (pintype "bidirectional"))
    )
    (net (code "118") (name "Net-(U2-Y2)") (class "Default")
      (node (ref "J1") (pin "4") (pinfunction "4_4") (pintype "passive"))
      (node (ref "R4") (pin "1") (pinfunction "1_1") (pintype "passive"))
      (node (ref "U2") (pin "15") (pinfunction "Y2_15") (pintype "bidirectional"))
    )
    (net (code "119") (name "Net-(U2-Y3)") (class "Default")
      (node (ref "J1") (pin "1") (pinfunction "1_1") (pintype "passive"))
      (node (ref "R3") (pin "1") (pinfunction "1_1") (pintype "passive"))
      (node (ref "U2") (pin "12") (pinfunction "Y3_12") (pintype "bidirectional"))
    )
    (net (code "120") (name "Net-(U2-Y4)") (class "Default")
      (node (ref "J1") (pin "5") (pinfunction "5_5") (pintype "passive"))
      (node (ref "R2") (pin "1") (pinfunction "1_1") (pintype "passive"))
      (node (ref "U2") (pin "1") (pinfunction "Y4_1") (pintype "bidirectional"))
    )
    (net (code "121") (name "Net-(U2-Y5)") (class "Default")
      (node (ref "J1") (pin "6") (pinfunction "6_6") (pintype "passive"))
      (node (ref "R1") (pin "1") (pinfunction "1_1") (pintype "passive"))
      (node (ref "U2") (pin "5") (pinfunction "Y5_5") (pintype "bidirectional"))
    )
    (net (code "122") (name "Net-(U6-C_FILT)") (class "Default")
      (node (ref "C6") (pin "1") (pinfunction "1_1") (pintype "passive"))
      (node (ref "U6") (pin "16") (pinfunction "C_FILT_16") (pintype "passive"))
    )
    (net (code "123") (name "Net-(U6-R_EXT)") (class "Default")
      (node (ref "R23") (pin "2") (pinfunction "2_2") (pintype "passive"))
      (node (ref "U6") (pin "6") (pinfunction "R_EXT_6") (pintype "passive"))
    )
    (net (code "124") (name "Net-(U8-IREF)") (class "Default")
      (node (ref "R25") (pin "1") (pinfunction "1_1") (pintype "passive"))
      (node (ref "U8") (pin "27") (pinfunction "IREF_27") (pintype "passive"))
    )
    (net (code "125") (name "VBatt") (class "Default")
      (node (ref "D5") (pin "1") (pinfunction "C_1") (pintype "passive"))
      (node (ref "PMOS2") (pin "2") (pinfunction "S_2") (pintype "passive"))
      (node (ref "R30") (pin "1") (pinfunction "1_1") (pintype "passive"))
    )
    (net (code "126") (name "Vin") (class "Default")
      (node (ref "C7") (pin "2") (pinfunction "2_2") (pintype "passive"))
      (node (ref "J6") (pin "2") (pinfunction "2_2") (pintype "passive"))
      (node (ref "PMOS1") (pin "3") (pinfunction "D_3") (pintype "passive"))
      (node (ref "PMOS2") (pin "3") (pinfunction "D_3") (pintype "passive"))
      (node (ref "U7") (pin "3") (pinfunction "VIN_3") (pintype "input"))
    )
    (net (code "127") (name "Vusb") (class "Default")
      (node (ref "J7") (pin "5") (pinfunction "GND_5") (pintype "power_in"))
      (node (ref "PMOS1") (pin "2") (pinfunction "S_2") (pintype "passive"))
      (node (ref "R29") (pin "1") (pinfunction "1_1") (pintype "passive"))
    )
    (net (code "128") (name "unconnected-(D3-B_C-Pad2)") (class "Default")
      (node (ref "D3") (pin "2") (pinfunction "B_C_2") (pintype "passive"))
    )
    (net (code "129") (name "unconnected-(DS2A-NC-Pad10)") (class "Default")
      (node (ref "DS2") (pin "10") (pinfunction "NC_10") (pintype "passive"))
    )
    (net (code "130") (name "unconnected-(DS2A-NC-Pad11)") (class "Default")
      (node (ref "DS2") (pin "11") (pinfunction "NC_11") (pintype "passive"))
    )
    (net (code "131") (name "unconnected-(DS2A-NC-Pad12)") (class "Default")
      (node (ref "DS2") (pin "12") (pinfunction "NC_12") (pintype "passive"))
    )
    (net (code "132") (name "unconnected-(DS2A-NC-Pad13)") (class "Default")
      (node (ref "DS2") (pin "13") (pinfunction "NC_13") (pintype "passive"))
    )
    (net (code "133") (name "unconnected-(DS2B-NC-Pad14)") (class "Default")
      (node (ref "DS2") (pin "14") (pinfunction "NC_14") (pintype "passive"))
    )
    (net (code "134") (name "unconnected-(DS2B-NC-Pad15)") (class "Default")
      (node (ref "DS2") (pin "15") (pinfunction "NC_15") (pintype "passive"))
    )
    (net (code "135") (name "unconnected-(DS2B-NC-Pad16)") (class "Default")
      (node (ref "DS2") (pin "16") (pinfunction "NC_16") (pintype "passive"))
    )
    (net (code "136") (name "unconnected-(DS2B-NC-Pad17)") (class "Default")
      (node (ref "DS2") (pin "17") (pinfunction "NC_17") (pintype "passive"))
    )
    (net (code "137") (name "unconnected-(J7-D--Pad2)") (class "Default")
      (node (ref "J7") (pin "2") (pinfunction "D-_2") (pintype "passive"))
    )
    (net (code "138") (name "unconnected-(J8-Pad9)") (class "Default")
      (node (ref "J8") (pin "9") (pinfunction "9_9") (pintype "passive"))
    )
    (net (code "139") (name "unconnected-(U1A-PB4-Pad40)") (class "Default")
      (node (ref "U1") (pin "40") (pinfunction "PB4_40") (pintype "bidirectional"))
    )
    (net (code "140") (name "unconnected-(U3-2A-Pad7)") (class "Default")
      (node (ref "U3") (pin "7") (pinfunction "2A_7") (pintype "bidirectional"))
    )
    (net (code "141") (name "unconnected-(U3-2B1-Pad5)") (class "Default")
      (node (ref "U3") (pin "5") (pinfunction "2B1_5") (pintype "bidirectional"))
    )
    (net (code "142") (name "unconnected-(U3-2B2-Pad6)") (class "Default")
      (node (ref "U3") (pin "6") (pinfunction "2B2_6") (pintype "bidirectional"))
    )
    (net (code "143") (name "unconnected-(U3-3A-Pad9)") (class "Default")
      (node (ref "U3") (pin "9") (pinfunction "3A_9") (pintype "bidirectional"))
    )
    (net (code "144") (name "unconnected-(U3-3B1-Pad11)") (class "Default")
      (node (ref "U3") (pin "11") (pinfunction "3B1_11") (pintype "bidirectional"))
    )
    (net (code "145") (name "unconnected-(U3-3B2-Pad10)") (class "Default")
      (node (ref "U3") (pin "10") (pinfunction "3B2_10") (pintype "bidirectional"))
    )
    (net (code "146") (name "unconnected-(U3-4A-Pad12)") (class "Default")
      (node (ref "U3") (pin "12") (pinfunction "4A_12") (pintype "bidirectional"))
    )
    (net (code "147") (name "unconnected-(U3-4B1-Pad14)") (class "Default")
      (node (ref "U3") (pin "14") (pinfunction "4B1_14") (pintype "bidirectional"))
    )
    (net (code "148") (name "unconnected-(U3-4B2-Pad13)") (class "Default")
      (node (ref "U3") (pin "13") (pinfunction "4B2_13") (pintype "bidirectional"))
    )
    (net (code "149") (name "unconnected-(U5-Y6-Pad2)") (class "Default")
      (node (ref "U5") (pin "2") (pinfunction "Y6_2") (pintype "bidirectional"))
    )
    (net (code "150") (name "unconnected-(U5-Y7-Pad4)") (class "Default")
      (node (ref "U5") (pin "4") (pinfunction "Y7_4") (pintype "bidirectional"))
    )
    (net (code "151") (name "unconnected-(U6-IN-Pad17)") (class "Default")
      (node (ref "U6") (pin "17") (pinfunction "IN_17") (pintype "input+no_connect"))
    )
    (net (code "152") (name "unconnected-(U8-SOUT-Pad24)") (class "Default")
      (node (ref "U8") (pin "24") (pinfunction "SOUT_24") (pintype "output"))
    )
    (net (code "153") (name "unconnected-(U8-XERR-Pad23)") (class "Default")
      (node (ref "U8") (pin "23") (pinfunction "XERR_23") (pintype "output"))
    )
    (net (code "154") (name "unconnected-(U9-I{slash}O3-Pad4)") (class "Default")
      (node (ref "U9") (pin "4") (pinfunction "I/O3_4") (pintype "passive"))
    )
    (net (code "155") (name "unconnected-(U9-I{slash}O4-Pad6)") (class "Default")
      (node (ref "U9") (pin "6") (pinfunction "I/O4_6") (pintype "passive"))
    )
  )
)
